# Project_Arduino_DUE_shield.net
KiCad netlist of a schematic drawn in Altium Designer
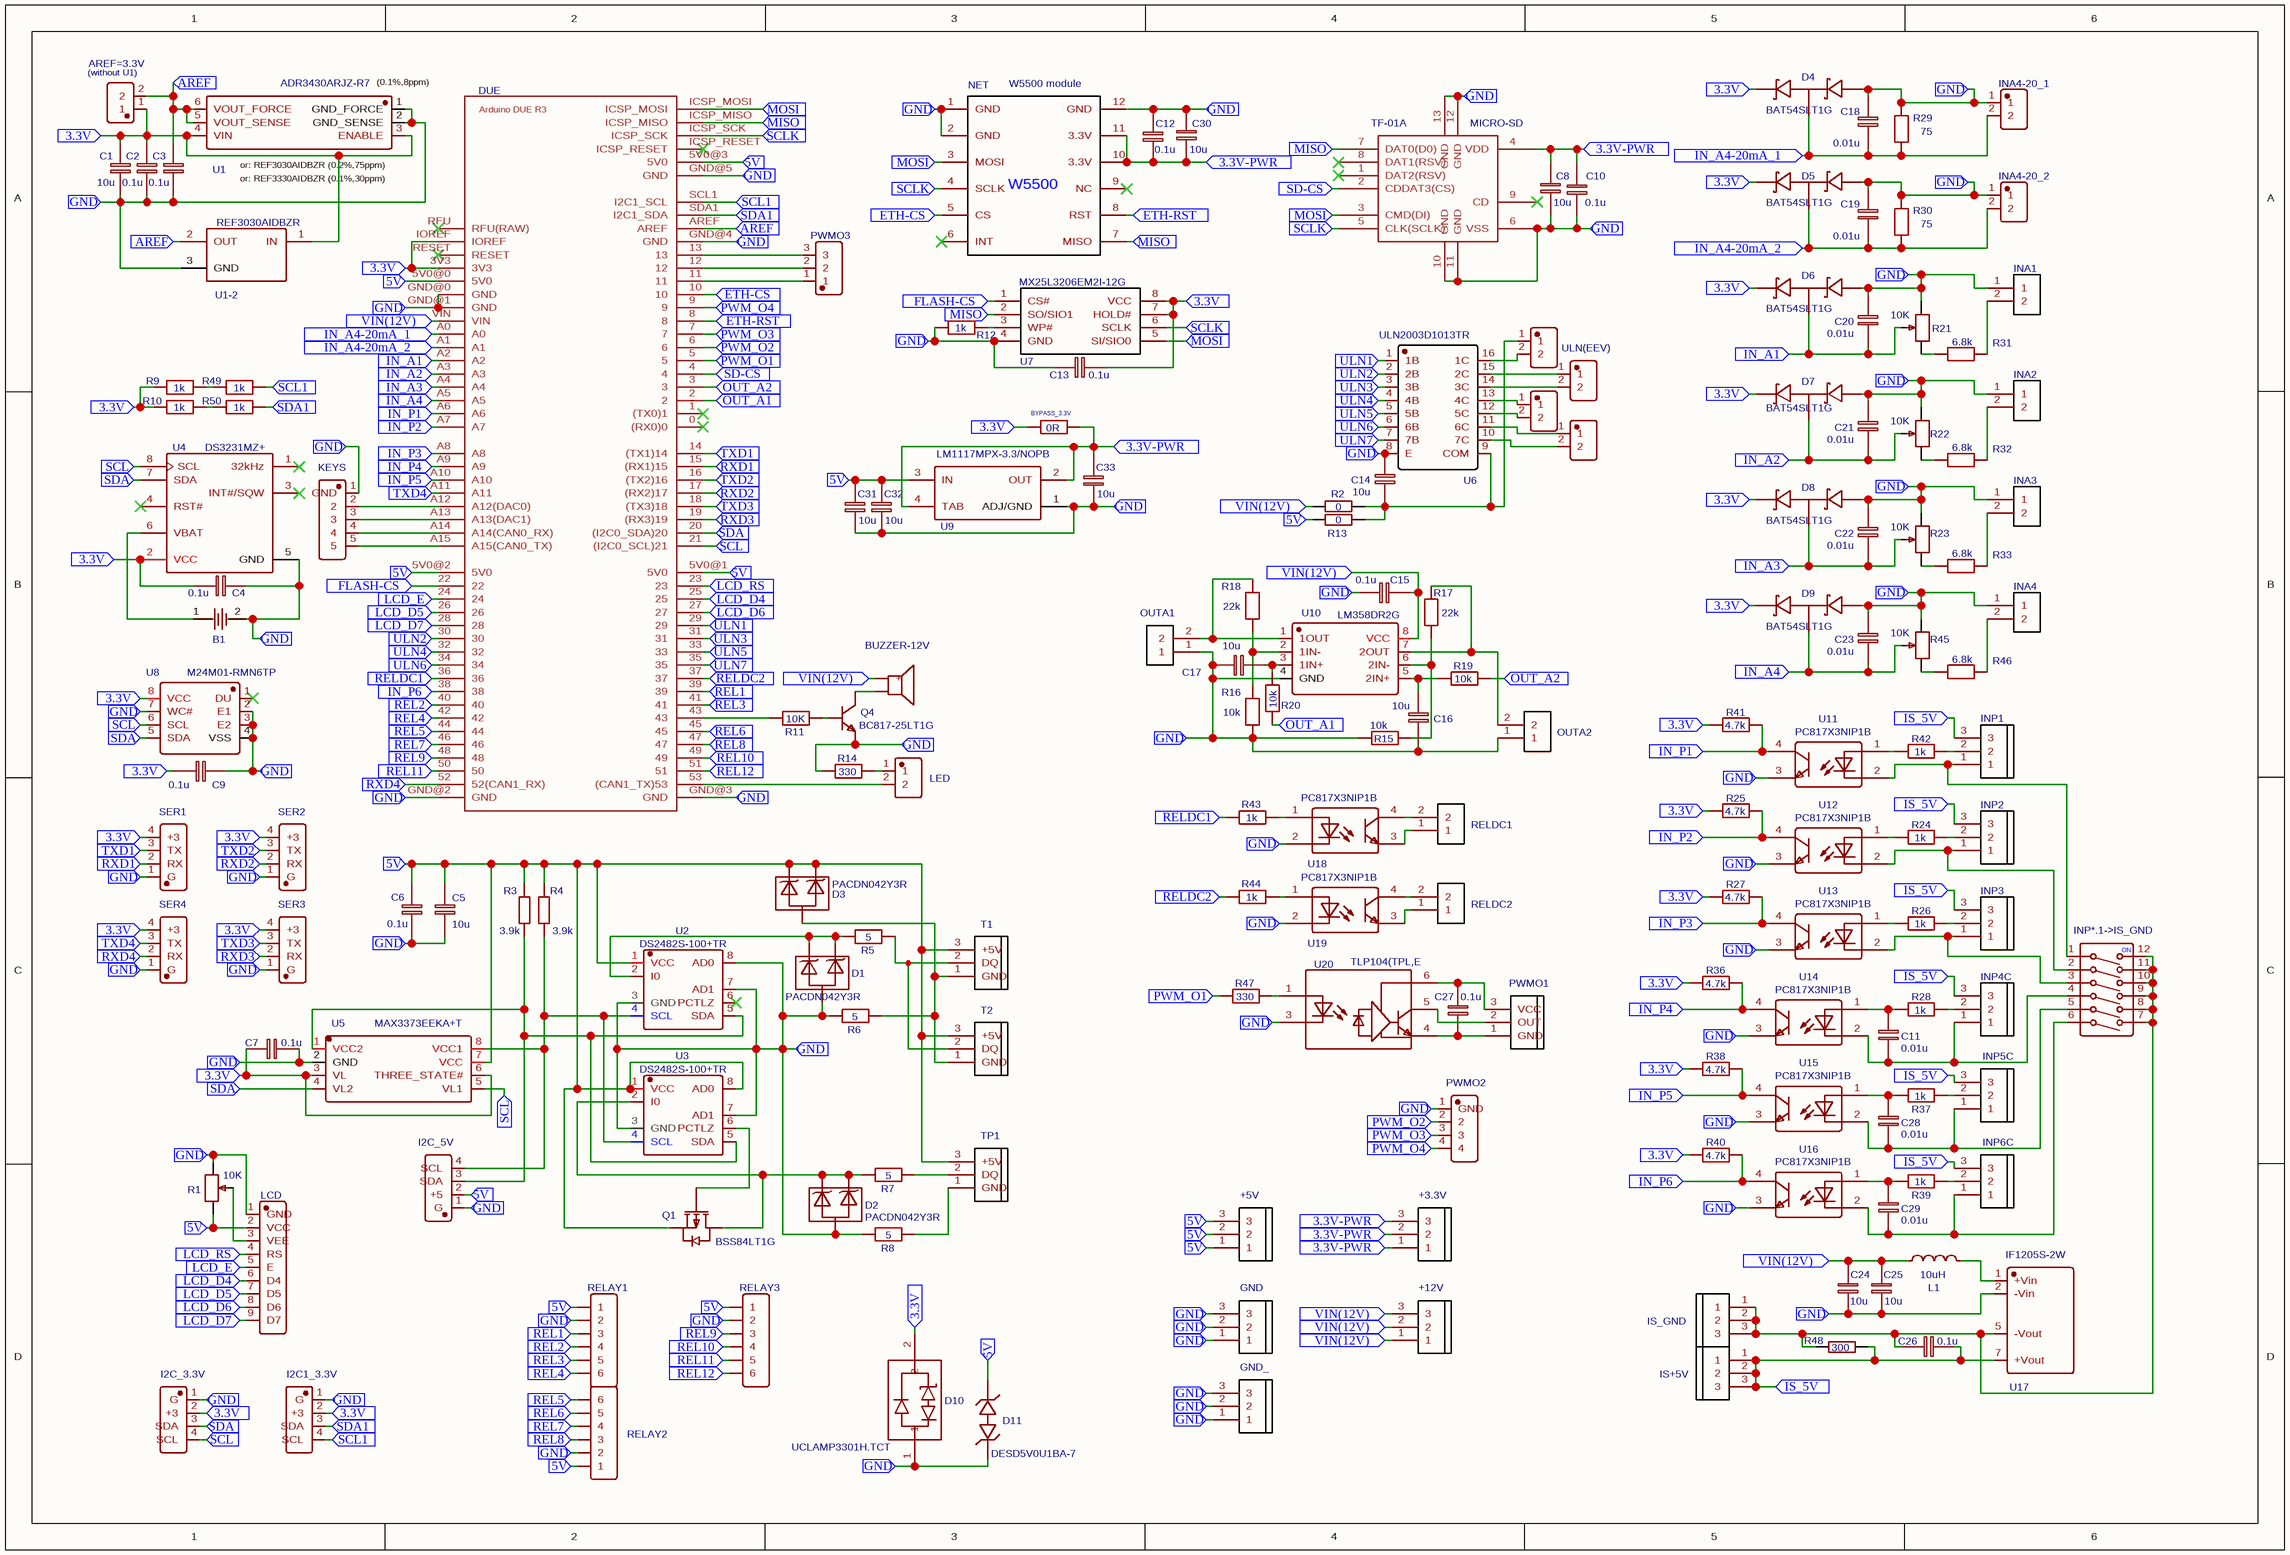
[diagram p0: Project_Arduino DUE shield.schdoc]

(export (version "E")
  (design (tool "Eeschema 10.0.6"))
  (components
    (comp (ref "+3.3V")
      (value "KF128L-5.08-3P")
      (fields (field (name "BOM_SUPPLIER PART") "C474941"))
      (libsource (lib "altium-import") (part "root_3_KF128L-5.08-3P_"))
    )
    (comp (ref "+5V")
      (value "KF128L-5.08-3P")
      (fields (field (name "BOM_SUPPLIER PART") "C474941"))
      (libsource (lib "altium-import") (part "root_3_KF128L-5.08-3P_"))
    )
    (comp (ref "+12V")
      (value "KF128L-5.08-3P")
      (fields (field (name "BOM_SUPPLIER PART") "C474941"))
      (libsource (lib "altium-import") (part "root_3_KF128L-5.08-3P_"))
    )
    (comp (ref "AREF=3.3V")
      (value "A2541WV-2P")
      (fields (field (name "BOM_SUPPLIER PART") "C225477") (field (name "CONTRIBUTOR") "LCSC"))
      (libsource (lib "altium-import") (part "root_2_A2541WV-2P_"))
    )
    (comp (ref "B1")
      (value "CR2032-BS-2-1")
      (fields (field (name "BOM_MANUFACTURER PART") "BS-2-1") (field (name "BOM_SUPPLIER PART") "C70376"))
      (libsource (lib "altium-import") (part "root_0_CR2032-BS-2-1_"))
    )
    (comp (ref "BUZZER-12V")
      (value "TMB12A12")
      (fields (field (name "BOM_SUPPLIER PART") "C96079"))
      (libsource (lib "altium-import") (part "root_0_TMB12A12_"))
    )
    (comp (ref "BYPASS_3.3V")
      (value "0R")
      (fields (field (name "CONTRIBUTOR") "LCEDA_Lib"))
      (libsource (lib "altium-import") (part "root_0_0R_"))
    )
    (comp (ref "C1")
      (value "10u")
      (fields
        (field (name "BOM_MANUFACTURER PART") "CL21A106KAYNNNE")
        (field (name "BOM_SUPPLIER PART") "C15850")
      )
      (libsource (lib "altium-import") (part "root_0_10u_"))
    )
    (comp (ref "C2")
      (value "0.1u")
      (fields
        (field (name "BOM_MANUFACTURER PART") "CC0603KRX7R9BB104")
        (field (name "BOM_SUPPLIER PART") "C14663")
      )
      (libsource (lib "") (part "root_0_0.1u__1"))
    )
    (comp (ref "C3")
      (value "0.1u")
      (fields
        (field (name "BOM_MANUFACTURER PART") "CC0603KRX7R9BB104")
        (field (name "BOM_SUPPLIER PART") "C14663")
      )
      (libsource (lib "") (part "root_0_0.1u__1"))
    )
    (comp (ref "C4")
      (value "0.1u")
      (fields
        (field (name "BOM_MANUFACTURER PART") "CC0603KRX7R9BB104")
        (field (name "BOM_SUPPLIER PART") "C14663")
      )
      (libsource (lib "altium-import") (part "root_3_0.1u_"))
    )
    (comp (ref "C5")
      (value "10u")
      (fields
        (field (name "BOM_MANUFACTURER PART") "CL21A106KAYNNNE")
        (field (name "BOM_SUPPLIER PART") "C15850")
      )
      (libsource (lib "altium-import") (part "root_0_10u_"))
    )
    (comp (ref "C6")
      (value "0.1u")
      (fields
        (field (name "BOM_MANUFACTURER PART") "CC0603KRX7R9BB104")
        (field (name "BOM_SUPPLIER PART") "C14663")
      )
      (libsource (lib "") (part "root_0_0.1u__1"))
    )
    (comp (ref "C7")
      (value "0.1u")
      (fields
        (field (name "BOM_MANUFACTURER PART") "CC0603KRX7R9BB104")
        (field (name "BOM_SUPPLIER PART") "C14663")
      )
      (libsource (lib "") (part "root_1_0.1u__1"))
    )
    (comp (ref "C8")
      (value "10u")
      (fields
        (field (name "BOM_SUPPLIER PART") "C15850")
        (field (name "BOM_MANUFACTURER PART") "CL21A106KAYNNNE")
        (field (name "CONTRIBUTOR") "LCEDA_Lib")
      )
      (libsource (lib "altium-import") (part "root_3_10u_"))
    )
    (comp (ref "C9")
      (value "0.1u")
      (fields
        (field (name "BOM_MANUFACTURER PART") "CC0603KRX7R9BB104")
        (field (name "BOM_SUPPLIER PART") "C14663")
      )
      (libsource (lib "altium-import") (part "root_3_0.1u_"))
    )
    (comp (ref "C10")
      (value "0.1u")
      (fields
        (field (name "BOM_SUPPLIER PART") "C14663")
        (field (name "BOM_MANUFACTURER PART") "CC0603KRX7R9BB104")
        (field (name "CONTRIBUTOR") "LCEDA_Lib")
      )
      (libsource (lib "altium-import") (part "root_1_0.1u_"))
    )
    (comp (ref "C11")
      (value "0.01u")
      (fields
        (field (name "BOM_SUPPLIER PART") "C57112")
        (field (name "BOM_MANUFACTURER PART") "0603B103K500NT")
        (field (name "CONTRIBUTOR") "LCEDA_Lib")
      )
      (libsource (lib "altium-import") (part "root_3_0.01u_"))
    )
    (comp (ref "C12")
      (value "0.1u")
      (fields
        (field (name "BOM_SUPPLIER PART") "C14663")
        (field (name "BOM_MANUFACTURER PART") "CC0603KRX7R9BB104")
        (field (name "CONTRIBUTOR") "LCEDA_Lib")
      )
      (libsource (lib "altium-import") (part "root_1_0.1u_"))
    )
    (comp (ref "C13")
      (value "0.1u")
      (fields
        (field (name "BOM_SUPPLIER PART") "C14663")
        (field (name "BOM_MANUFACTURER PART") "CC0603KRX7R9BB104")
        (field (name "CONTRIBUTOR") "LCEDA_Lib")
      )
      (libsource (lib "altium-import") (part "root_0_0.1u_"))
    )
    (comp (ref "C14")
      (value "10u")
      (fields
        (field (name "BOM_MANUFACTURER PART") "CL21A106KAYNNNE")
        (field (name "BOM_SUPPLIER PART") "C15850")
      )
      (libsource (lib "") (part "root_0_10u__1"))
    )
    (comp (ref "C15")
      (value "0.1u")
      (fields
        (field (name "BOM_MANUFACTURER PART") "CC0603KRX7R9BB104")
        (field (name "BOM_SUPPLIER PART") "C14663")
      )
      (libsource (lib "") (part "root_3_0.1u__1"))
    )
    (comp (ref "C16")
      (value "10u")
      (fields
        (field (name "BOM_MANUFACTURER PART") "CL21A106KAYNNNE")
        (field (name "BOM_SUPPLIER PART") "C15850")
      )
      (libsource (lib "altium-import") (part "root_0_10u_"))
    )
    (comp (ref "C17")
      (value "10u")
      (fields
        (field (name "BOM_MANUFACTURER PART") "CL21A106KAYNNNE")
        (field (name "BOM_SUPPLIER PART") "C15850")
      )
      (libsource (lib "") (part "root_1_10u__1"))
    )
    (comp (ref "C18")
      (value "0.01u")
      (fields
        (field (name "BOM_MANUFACTURER PART") "0603B103K500NT")
        (field (name "BOM_SUPPLIER PART") "C57112")
      )
      (libsource (lib "altium-import") (part "root_0_0.01u_"))
    )
    (comp (ref "C19")
      (value "0.01u")
      (fields
        (field (name "BOM_MANUFACTURER PART") "0603B103K500NT")
        (field (name "BOM_SUPPLIER PART") "C57112")
      )
      (libsource (lib "altium-import") (part "root_0_0.01u_"))
    )
    (comp (ref "C20")
      (value "0.01u")
      (fields
        (field (name "BOM_MANUFACTURER PART") "0603B103K500NT")
        (field (name "BOM_SUPPLIER PART") "C57112")
      )
      (libsource (lib "altium-import") (part "root_0_0.01u_"))
    )
    (comp (ref "C21")
      (value "0.01u")
      (fields
        (field (name "BOM_MANUFACTURER PART") "0603B103K500NT")
        (field (name "BOM_SUPPLIER PART") "C57112")
      )
      (libsource (lib "altium-import") (part "root_0_0.01u_"))
    )
    (comp (ref "C22")
      (value "0.01u")
      (fields
        (field (name "BOM_MANUFACTURER PART") "0603B103K500NT")
        (field (name "BOM_SUPPLIER PART") "C57112")
      )
      (libsource (lib "altium-import") (part "root_0_0.01u_"))
    )
    (comp (ref "C23")
      (value "0.01u")
      (fields
        (field (name "BOM_MANUFACTURER PART") "0603B103K500NT")
        (field (name "BOM_SUPPLIER PART") "C57112")
      )
      (libsource (lib "altium-import") (part "root_0_0.01u_"))
    )
    (comp (ref "C24")
      (value "10u")
      (fields
        (field (name "BOM_SUPPLIER PART") "C15850")
        (field (name "BOM_MANUFACTURER PART") "CL21A106KAYNNNE")
        (field (name "CONTRIBUTOR") "LCEDA_Lib")
      )
      (libsource (lib "altium-import") (part "root_1_10u_"))
    )
    (comp (ref "C25")
      (value "10u")
      (fields
        (field (name "BOM_SUPPLIER PART") "C15850")
        (field (name "BOM_MANUFACTURER PART") "CL21A106KAYNNNE")
        (field (name "CONTRIBUTOR") "LCEDA_Lib")
      )
      (libsource (lib "altium-import") (part "root_1_10u_"))
    )
    (comp (ref "C26")
      (value "0.1u")
      (fields
        (field (name "BOM_MANUFACTURER PART") "CC0603KRX7R9BB104")
        (field (name "BOM_SUPPLIER PART") "C14663")
      )
      (libsource (lib "") (part "root_1_0.1u__2"))
    )
    (comp (ref "C27")
      (value "0.1u")
      (fields
        (field (name "BOM_MANUFACTURER PART") "CC0603KRX7R9BB104")
        (field (name "BOM_SUPPLIER PART") "C14663")
      )
      (libsource (lib "") (part "root_0_0.1u__2"))
    )
    (comp (ref "C28")
      (value "0.01u")
      (fields
        (field (name "BOM_SUPPLIER PART") "C57112")
        (field (name "BOM_MANUFACTURER PART") "0603B103K500NT")
        (field (name "CONTRIBUTOR") "LCEDA_Lib")
      )
      (libsource (lib "altium-import") (part "root_3_0.01u_"))
    )
    (comp (ref "C29")
      (value "0.01u")
      (fields
        (field (name "BOM_SUPPLIER PART") "C57112")
        (field (name "BOM_MANUFACTURER PART") "0603B103K500NT")
        (field (name "CONTRIBUTOR") "LCEDA_Lib")
      )
      (libsource (lib "altium-import") (part "root_3_0.01u_"))
    )
    (comp (ref "C30")
      (value "10u")
      (fields
        (field (name "BOM_SUPPLIER PART") "C15850")
        (field (name "BOM_MANUFACTURER PART") "CL21A106KAYNNNE")
        (field (name "CONTRIBUTOR") "LCEDA_Lib")
      )
      (libsource (lib "altium-import") (part "root_3_10u_"))
    )
    (comp (ref "C31")
      (value "10u")
      (fields
        (field (name "BOM_MANUFACTURER PART") "CL21A106KAYNNNE")
        (field (name "BOM_SUPPLIER PART") "C15850")
      )
      (libsource (lib "altium-import") (part "root_2_10u_"))
    )
    (comp (ref "C32")
      (value "10u")
      (fields
        (field (name "BOM_MANUFACTURER PART") "CL21A106KAYNNNE")
        (field (name "BOM_SUPPLIER PART") "C15850")
      )
      (libsource (lib "altium-import") (part "root_2_10u_"))
    )
    (comp (ref "C33")
      (value "10u")
      (fields
        (field (name "BOM_MANUFACTURER PART") "CL21A106KAYNNNE")
        (field (name "BOM_SUPPLIER PART") "C15850")
      )
      (libsource (lib "altium-import") (part "root_2_10u_"))
    )
    (comp (ref "D1")
      (value "PACDN042Y3R")
      (fields (field (name "BOM_SUPPLIER PART") "C233486") (field (name "CONTRIBUTOR") "LCSC"))
      (libsource (lib "altium-import") (part "root_2_PACDN042Y3R_"))
    )
    (comp (ref "D2")
      (value "PACDN042Y3R")
      (fields (field (name "BOM_SUPPLIER PART") "C233486") (field (name "CONTRIBUTOR") "LCSC"))
      (libsource (lib "altium-import") (part "root_2_PACDN042Y3R_"))
    )
    (comp (ref "D3")
      (value "PACDN042Y3R")
      (fields (field (name "BOM_SUPPLIER PART") "C233486") (field (name "CONTRIBUTOR") "LCSC"))
      (libsource (lib "altium-import") (part "root_2_PACDN042Y3R_"))
    )
    (comp (ref "D4")
      (value "BAT54SLT1G")
      (fields (field (name "BOM_SUPPLIER PART") "C19726"))
      (libsource (lib "altium-import") (part "root_0_BAT54SLT1G_"))
    )
    (comp (ref "D5")
      (value "BAT54SLT1G")
      (fields (field (name "BOM_SUPPLIER PART") "C19726"))
      (libsource (lib "altium-import") (part "root_0_BAT54SLT1G_"))
    )
    (comp (ref "D6")
      (value "BAT54SLT1G")
      (fields (field (name "BOM_SUPPLIER PART") "C19726"))
      (libsource (lib "altium-import") (part "root_0_BAT54SLT1G_"))
    )
    (comp (ref "D7")
      (value "BAT54SLT1G")
      (fields (field (name "BOM_SUPPLIER PART") "C19726"))
      (libsource (lib "altium-import") (part "root_0_BAT54SLT1G_"))
    )
    (comp (ref "D8")
      (value "BAT54SLT1G")
      (fields (field (name "BOM_SUPPLIER PART") "C19726"))
      (libsource (lib "altium-import") (part "root_0_BAT54SLT1G_"))
    )
    (comp (ref "D9")
      (value "BAT54SLT1G")
      (fields (field (name "BOM_SUPPLIER PART") "C19726"))
      (libsource (lib "altium-import") (part "root_0_BAT54SLT1G_"))
    )
    (comp (ref "D10")
      (value "UCLAMP3301H.TCT")
      (fields (field (name "BOM_SUPPLIER PART") "C117558") (field (name "CONTRIBUTOR") "LCSC"))
      (libsource (lib "altium-import") (part "root_1_UCLAMP3301H.TCT_"))
    )
    (comp (ref "D11")
      (value "DESD5V0U1BA-7")
      (fields (field (name "BOM_SUPPLIER PART") "C460442") (field (name "CONTRIBUTOR") "LCSC"))
      (libsource (lib "altium-import") (part "root_1_DESD5V0U1BA-7_"))
    )
    (comp (ref "DUE")
      (value "PA_DUE_BRD")
      (description "PatternAgents Due Shield Board Pattern")
      (fields (field (name "BOM_MANUFACTURER PART") "?") (field (name "CONTRIBUTOR") "PatternAgents"))
      (libsource (lib "altium-import") (part "root_0_PA_DUE_BRD_"))
    )
    (comp (ref "GND")
      (value "KF128L-5.08-3P")
      (fields (field (name "BOM_SUPPLIER PART") "C474941"))
      (libsource (lib "altium-import") (part "root_3_KF128L-5.08-3P_"))
    )
    (comp (ref "GND_")
      (value "KF128L-5.08-3P")
      (fields (field (name "BOM_SUPPLIER PART") "C474941"))
      (libsource (lib "altium-import") (part "root_3_KF128L-5.08-3P_"))
    )
    (comp (ref "I2C1_3.3V")
      (value "A2541WV-4P")
      (fields (field (name "BOM_SUPPLIER PART") "C225479") (field (name "CONTRIBUTOR") "LCSC"))
      (libsource (lib "") (part "root_1_A2541WV-4P__2"))
    )
    (comp (ref "I2C_3.3V")
      (value "A2541WV-4P")
      (fields (field (name "BOM_SUPPLIER PART") "C225479") (field (name "CONTRIBUTOR") "LCSC"))
      (libsource (lib "") (part "root_1_A2541WV-4P__2"))
    )
    (comp (ref "I2C_5V")
      (value "A2541WV-4P")
      (fields (field (name "BOM_SUPPLIER PART") "C225479") (field (name "CONTRIBUTOR") "LCSC"))
      (libsource (lib "altium-import") (part "root_1_A2541WV-4P_"))
    )
    (comp (ref "INA1")
      (value "KF128L-5.08-2P")
      (fields (field (name "BOM_SUPPLIER PART") "C474940"))
      (libsource (lib "altium-import") (part "root_3_KF128L-5.08-2P_"))
    )
    (comp (ref "INA2")
      (value "KF128L-5.08-2P")
      (fields (field (name "BOM_SUPPLIER PART") "C474940"))
      (libsource (lib "altium-import") (part "root_3_KF128L-5.08-2P_"))
    )
    (comp (ref "INA3")
      (value "KF128L-5.08-2P")
      (fields (field (name "BOM_SUPPLIER PART") "C474940"))
      (libsource (lib "altium-import") (part "root_3_KF128L-5.08-2P_"))
    )
    (comp (ref "INA4")
      (value "KF128L-5.08-2P")
      (fields (field (name "BOM_SUPPLIER PART") "C474940"))
      (libsource (lib "altium-import") (part "root_3_KF128L-5.08-2P_"))
    )
    (comp (ref "INA4-20_1")
      (value "KF128L-3.5-2P")
      (fields (field (name "BOM_SUPPLIER PART") "C474930") (field (name "CONTRIBUTOR") "LCSC"))
      (libsource (lib "altium-import") (part "root_0_KF128L-3.5-2P_"))
    )
    (comp (ref "INA4-20_2")
      (value "KF128L-3.5-2P")
      (fields (field (name "BOM_SUPPLIER PART") "C474930") (field (name "CONTRIBUTOR") "LCSC"))
      (libsource (lib "altium-import") (part "root_0_KF128L-3.5-2P_"))
    )
    (comp (ref "INP*.1->IS_GND")
      (value "EM-06-Q")
      (fields (field (name "BOM_SUPPLIER PART") "C501580") (field (name "CONTRIBUTOR") "LCSC"))
      (libsource (lib "altium-import") (part "root_3_EM-06-Q_"))
    )
    (comp (ref "INP1")
      (value "KF128L-5.08-3P")
      (fields (field (name "BOM_SUPPLIER PART") "C474941"))
      (libsource (lib "altium-import") (part "root_3_KF128L-5.08-3P_"))
    )
    (comp (ref "INP2")
      (value "KF128L-5.08-3P")
      (fields (field (name "BOM_SUPPLIER PART") "C474941"))
      (libsource (lib "altium-import") (part "root_3_KF128L-5.08-3P_"))
    )
    (comp (ref "INP3")
      (value "KF128L-5.08-3P")
      (fields (field (name "BOM_SUPPLIER PART") "C474941"))
      (libsource (lib "altium-import") (part "root_3_KF128L-5.08-3P_"))
    )
    (comp (ref "INP4C")
      (value "KF128L-5.08-3P")
      (fields (field (name "BOM_SUPPLIER PART") "C474941"))
      (libsource (lib "altium-import") (part "root_3_KF128L-5.08-3P_"))
    )
    (comp (ref "INP5C")
      (value "KF128L-5.08-3P")
      (fields (field (name "BOM_SUPPLIER PART") "C474941"))
      (libsource (lib "altium-import") (part "root_3_KF128L-5.08-3P_"))
    )
    (comp (ref "INP6C")
      (value "KF128L-5.08-3P")
      (fields (field (name "BOM_SUPPLIER PART") "C474941"))
      (libsource (lib "altium-import") (part "root_3_KF128L-5.08-3P_"))
    )
    (comp (ref "IS+5V")
      (value "KF128L-5.08-3P")
      (fields (field (name "BOM_SUPPLIER PART") "C474941"))
      (libsource (lib "altium-import") (part "root_1_KF128L-5.08-3P_"))
    )
    (comp (ref "IS_GND")
      (value "KF128L-5.08-3P")
      (fields (field (name "BOM_SUPPLIER PART") "C474941"))
      (libsource (lib "altium-import") (part "root_1_KF128L-5.08-3P_"))
    )
    (comp (ref "KEYS")
      (value "A2541WV-5P")
      (fields (field (name "BOM_SUPPLIER PART") "C225480") (field (name "CONTRIBUTOR") "LCSC"))
      (libsource (lib "altium-import") (part "root_1_A2541WV-5P_"))
    )
    (comp (ref "L1")
      (value "10uH")
      (fields
        (field (name "BOM_MANUFACTURER PART") "FNR4018S100MT")
        (field (name "BOM_SUPPLIER PART") "C167808")
        (field (name "CONTRIBUTOR") "LCSC")
      )
      (libsource (lib "altium-import") (part "root_0_10uH_"))
    )
    (comp (ref "LCD")
      (value "PZ254V-11-09P")
      (fields (field (name "BOM_SUPPLIER PART") "C492408") (field (name "CONTRIBUTOR") "LCSC"))
      (libsource (lib "altium-import") (part "root_0_PZ254V-11-09P_"))
    )
    (comp (ref "LED")
      (value "A2541WV-2P")
      (fields (field (name "BOM_SUPPLIER PART") "C225477") (field (name "CONTRIBUTOR") "LCSC"))
      (libsource (lib "altium-import") (part "root_0_A2541WV-2P_"))
    )
    (comp (ref "MICRO-SD")
      (value "TF-01A")
      (fields (field (name "BOM_MANUFACTURER PART") "TF-15×15") (field (name "BOM_SUPPLIER PART") "C111196"))
      (libsource (lib "altium-import") (part "root_0_TF-01A_"))
    )
    (comp (ref "NET")
      (value "W5500 module")
      (fields (field (name "BOM_MANUFACTURER PART") "?") (field (name "CONTRIBUTOR") "RubenDijk"))
      (libsource (lib "altium-import") (part "root_0_W5500 module_"))
    )
    (comp (ref "OUTA1")
      (value "KF128L-5.08-2P")
      (fields
        (field (name "BOM_MANUFACTURER PART") "KF128L-3.5-2P")
        (field (name "BOM_SUPPLIER PART") "C474930")
      )
      (libsource (lib "altium-import") (part "root_1_KF128L-5.08-2P_"))
    )
    (comp (ref "OUTA2")
      (value "KF128L-5.08-2P")
      (fields
        (field (name "BOM_MANUFACTURER PART") "KF128L-3.5-2P")
        (field (name "BOM_SUPPLIER PART") "C474930")
      )
      (libsource (lib "") (part "root_3_KF128L-5.08-2P__1"))
    )
    (comp (ref "PWMO1")
      (value "KF128L-5.08-3P")
      (fields (field (name "BOM_SUPPLIER PART") "C474941"))
      (libsource (lib "altium-import") (part "root_3_KF128L-5.08-3P_"))
    )
    (comp (ref "PWMO2")
      (value "A2541WV-4P")
      (fields (field (name "BOM_SUPPLIER PART") "C225479") (field (name "CONTRIBUTOR") "LCSC"))
      (libsource (lib "") (part "root_1_A2541WV-4P__1"))
    )
    (comp (ref "PWMO3")
      (value "A2541WV-3P")
      (fields (field (name "BOM_SUPPLIER PART") "C225478") (field (name "CONTRIBUTOR") "LCSC"))
      (libsource (lib "altium-import") (part "root_3_A2541WV-3P_"))
    )
    (comp (ref "Q1")
      (value "BSS84LT1G")
      (fields (field (name "BOM_MANUFACTURER PART") "LBSS84LT1G") (field (name "BOM_SUPPLIER PART") "C8492"))
      (libsource (lib "altium-import") (part "root_3_BSS84LT1G_"))
    )
    (comp (ref "Q4")
      (value "BC817-25LT1G")
      (fields (field (name "BOM_SUPPLIER PART") "C82635"))
      (libsource (lib "altium-import") (part "root_0_BC817-25LT1G_"))
    )
    (comp (ref "R1")
      (value "10K")
      (fields
        (field (name "BOM_MANUFACTURER PART") "3314J-1-103E")
        (field (name "BOM_SUPPLIER PART") "C36376")
      )
      (libsource (lib "") (part "root_0_10K__1"))
    )
    (comp (ref "R2") (value "0") (libsource (lib "altium-import") (part "root_0_0_")))
    (comp (ref "R3")
      (value "3.9k")
      (fields
        (field (name "BOM_MANUFACTURER PART") "0603WAF3901T5E")
        (field (name "BOM_SUPPLIER PART") "C23018")
      )
      (libsource (lib "altium-import") (part "root_1_3.9k_"))
    )
    (comp (ref "R4")
      (value "3.9k")
      (fields
        (field (name "BOM_MANUFACTURER PART") "0603WAF3901T5E")
        (field (name "BOM_SUPPLIER PART") "C23018")
      )
      (libsource (lib "altium-import") (part "root_1_3.9k_"))
    )
    (comp (ref "R5")
      (value "5")
      (fields
        (field (name "BOM_SUPPLIER PART") "C25197")
        (field (name "BOM_MANUFACTURER PART") "0603WAF510KT5E")
        (field (name "CONTRIBUTOR") "LCEDA_Lib")
      )
      (libsource (lib "altium-import") (part "root_0_5_"))
    )
    (comp (ref "R6")
      (value "5")
      (fields
        (field (name "BOM_SUPPLIER PART") "C25197")
        (field (name "BOM_MANUFACTURER PART") "0603WAF510KT5E")
        (field (name "CONTRIBUTOR") "LCEDA_Lib")
      )
      (libsource (lib "altium-import") (part "root_0_5_"))
    )
    (comp (ref "R7")
      (value "5")
      (fields
        (field (name "BOM_SUPPLIER PART") "C25197")
        (field (name "BOM_MANUFACTURER PART") "0603WAF510KT5E")
        (field (name "CONTRIBUTOR") "LCEDA_Lib")
      )
      (libsource (lib "altium-import") (part "root_0_5_"))
    )
    (comp (ref "R8")
      (value "5")
      (fields
        (field (name "BOM_SUPPLIER PART") "C25197")
        (field (name "BOM_MANUFACTURER PART") "0603WAF510KT5E")
        (field (name "CONTRIBUTOR") "LCEDA_Lib")
      )
      (libsource (lib "altium-import") (part "root_0_5_"))
    )
    (comp (ref "R9")
      (value "1k")
      (fields
        (field (name "BOM_SUPPLIER PART") "C21190")
        (field (name "BOM_MANUFACTURER PART") "0603WAF1001T5E")
        (field (name "CONTRIBUTOR") "LCEDA_Lib")
      )
      (libsource (lib "") (part "root_0_1k__1"))
    )
    (comp (ref "R10")
      (value "1k")
      (fields
        (field (name "BOM_SUPPLIER PART") "C21190")
        (field (name "BOM_MANUFACTURER PART") "0603WAF1001T5E")
        (field (name "CONTRIBUTOR") "LCEDA_Lib")
      )
      (libsource (lib "") (part "root_0_1k__1"))
    )
    (comp (ref "R11")
      (value "10K")
      (fields
        (field (name "BOM_MANUFACTURER PART") "0603WAF1002T5E")
        (field (name "BOM_SUPPLIER PART") "C25804")
      )
      (libsource (lib "altium-import") (part "root_2_10K_"))
    )
    (comp (ref "R12")
      (value "1k")
      (fields
        (field (name "BOM_SUPPLIER PART") "C21190")
        (field (name "BOM_MANUFACTURER PART") "0603WAF1001T5E")
        (field (name "CONTRIBUTOR") "LCEDA_Lib")
      )
      (libsource (lib "") (part "root_0_1k__1"))
    )
    (comp (ref "R13") (value "0") (libsource (lib "altium-import") (part "root_0_0_")))
    (comp (ref "R14")
      (value "330")
      (fields
        (field (name "BOM_SUPPLIER PART") "C23138")
        (field (name "BOM_MANUFACTURER PART") "0603WAF3300T5E")
        (field (name "CONTRIBUTOR") "LCEDA_Lib")
      )
      (libsource (lib "altium-import") (part "root_2_330_"))
    )
    (comp (ref "R15")
      (value "10k")
      (fields
        (field (name "BOM_MANUFACTURER PART") "0603WAF1002T5E")
        (field (name "BOM_SUPPLIER PART") "C25804")
      )
      (libsource (lib "altium-import") (part "root_0_10k_"))
    )
    (comp (ref "R16")
      (value "10k")
      (fields
        (field (name "BOM_MANUFACTURER PART") "0603WAF1002T5E")
        (field (name "BOM_SUPPLIER PART") "C25804")
      )
      (libsource (lib "altium-import") (part "root_1_10k_"))
    )
    (comp (ref "R17")
      (value "22k")
      (fields
        (field (name "BOM_MANUFACTURER PART") "0603WAF2202T5E")
        (field (name "BOM_SUPPLIER PART") "C31850")
      )
      (libsource (lib "altium-import") (part "root_1_22k_"))
    )
    (comp (ref "R18")
      (value "22k")
      (fields
        (field (name "BOM_MANUFACTURER PART") "0603WAF2202T5E")
        (field (name "BOM_SUPPLIER PART") "C31850")
      )
      (libsource (lib "altium-import") (part "root_1_22k_"))
    )
    (comp (ref "R19")
      (value "10k")
      (fields
        (field (name "BOM_MANUFACTURER PART") "0603WAF1002T5E")
        (field (name "BOM_SUPPLIER PART") "C25804")
      )
      (libsource (lib "altium-import") (part "root_0_10k_"))
    )
    (comp (ref "R20")
      (value "10k")
      (fields
        (field (name "BOM_MANUFACTURER PART") "0603WAF1002T5E")
        (field (name "BOM_SUPPLIER PART") "C25804")
      )
      (libsource (lib "altium-import") (part "root_1_10k_"))
    )
    (comp (ref "R21")
      (value "10K")
      (fields
        (field (name "BOM_MANUFACTURER PART") "3314J-1-103E")
        (field (name "BOM_SUPPLIER PART") "C36376")
      )
      (libsource (lib "altium-import") (part "root_0_10K_"))
    )
    (comp (ref "R22")
      (value "10K")
      (fields
        (field (name "BOM_MANUFACTURER PART") "3314J-1-103E")
        (field (name "BOM_SUPPLIER PART") "C36376")
      )
      (libsource (lib "altium-import") (part "root_0_10K_"))
    )
    (comp (ref "R23")
      (value "10K")
      (fields
        (field (name "BOM_MANUFACTURER PART") "3314J-1-103E")
        (field (name "BOM_SUPPLIER PART") "C36376")
      )
      (libsource (lib "altium-import") (part "root_0_10K_"))
    )
    (comp (ref "R24")
      (value "1k")
      (fields
        (field (name "BOM_MANUFACTURER PART") "0603WAF1001T5E")
        (field (name "BOM_SUPPLIER PART") "C21190")
      )
      (libsource (lib "altium-import") (part "root_0_1k_"))
    )
    (comp (ref "R25")
      (value "4.7k")
      (fields
        (field (name "BOM_MANUFACTURER PART") "0603WAF4701T5E")
        (field (name "BOM_SUPPLIER PART") "C23162")
      )
      (libsource (lib "altium-import") (part "root_0_4.7k_"))
    )
    (comp (ref "R26")
      (value "1k")
      (fields
        (field (name "BOM_MANUFACTURER PART") "0603WAF1001T5E")
        (field (name "BOM_SUPPLIER PART") "C21190")
      )
      (libsource (lib "altium-import") (part "root_0_1k_"))
    )
    (comp (ref "R27")
      (value "4.7k")
      (fields
        (field (name "BOM_MANUFACTURER PART") "0603WAF4701T5E")
        (field (name "BOM_SUPPLIER PART") "C23162")
      )
      (libsource (lib "altium-import") (part "root_0_4.7k_"))
    )
    (comp (ref "R28")
      (value "1k")
      (fields
        (field (name "BOM_MANUFACTURER PART") "0603WAF1001T5E")
        (field (name "BOM_SUPPLIER PART") "C21190")
      )
      (libsource (lib "altium-import") (part "root_0_1k_"))
    )
    (comp (ref "R29")
      (value "75")
      (fields
        (field (name "BOM_MANUFACTURER PART") "0805W8F750JT5E")
        (field (name "BOM_SUPPLIER PART") "C20638")
      )
      (libsource (lib "altium-import") (part "root_3_75_"))
    )
    (comp (ref "R30")
      (value "75")
      (fields
        (field (name "BOM_MANUFACTURER PART") "0805W8F750JT5E")
        (field (name "BOM_SUPPLIER PART") "C20638")
      )
      (libsource (lib "altium-import") (part "root_3_75_"))
    )
    (comp (ref "R31")
      (value "6.8k")
      (fields
        (field (name "BOM_MANUFACTURER PART") "0603WAF6801T5E")
        (field (name "BOM_SUPPLIER PART") "C23212")
      )
      (libsource (lib "altium-import") (part "root_0_6.8k_"))
    )
    (comp (ref "R32")
      (value "6.8k")
      (fields
        (field (name "BOM_MANUFACTURER PART") "0603WAF6801T5E")
        (field (name "BOM_SUPPLIER PART") "C23212")
      )
      (libsource (lib "altium-import") (part "root_0_6.8k_"))
    )
    (comp (ref "R33")
      (value "6.8k")
      (fields
        (field (name "BOM_MANUFACTURER PART") "0603WAF6801T5E")
        (field (name "BOM_SUPPLIER PART") "C23212")
      )
      (libsource (lib "altium-import") (part "root_0_6.8k_"))
    )
    (comp (ref "R36")
      (value "4.7k")
      (fields
        (field (name "BOM_MANUFACTURER PART") "0603WAF4701T5E")
        (field (name "BOM_SUPPLIER PART") "C23162")
      )
      (libsource (lib "altium-import") (part "root_0_4.7k_"))
    )
    (comp (ref "R37")
      (value "1k")
      (fields
        (field (name "BOM_MANUFACTURER PART") "0603WAF1001T5E")
        (field (name "BOM_SUPPLIER PART") "C21190")
      )
      (libsource (lib "altium-import") (part "root_0_1k_"))
    )
    (comp (ref "R38")
      (value "4.7k")
      (fields
        (field (name "BOM_MANUFACTURER PART") "0603WAF4701T5E")
        (field (name "BOM_SUPPLIER PART") "C23162")
      )
      (libsource (lib "altium-import") (part "root_0_4.7k_"))
    )
    (comp (ref "R39")
      (value "1k")
      (fields
        (field (name "BOM_MANUFACTURER PART") "0603WAF1001T5E")
        (field (name "BOM_SUPPLIER PART") "C21190")
      )
      (libsource (lib "altium-import") (part "root_0_1k_"))
    )
    (comp (ref "R40")
      (value "4.7k")
      (fields
        (field (name "BOM_MANUFACTURER PART") "0603WAF4701T5E")
        (field (name "BOM_SUPPLIER PART") "C23162")
      )
      (libsource (lib "altium-import") (part "root_0_4.7k_"))
    )
    (comp (ref "R41")
      (value "4.7k")
      (fields
        (field (name "BOM_MANUFACTURER PART") "0603WAF4701T5E")
        (field (name "BOM_SUPPLIER PART") "C23162")
      )
      (libsource (lib "altium-import") (part "root_0_4.7k_"))
    )
    (comp (ref "R42")
      (value "1k")
      (fields
        (field (name "BOM_MANUFACTURER PART") "0603WAF1001T5E")
        (field (name "BOM_SUPPLIER PART") "C21190")
      )
      (libsource (lib "altium-import") (part "root_0_1k_"))
    )
    (comp (ref "R43")
      (value "1k")
      (fields
        (field (name "BOM_SUPPLIER PART") "C21190")
        (field (name "BOM_MANUFACTURER PART") "0603WAF1001T5E")
        (field (name "CONTRIBUTOR") "LCEDA_Lib")
      )
      (libsource (lib "") (part "root_0_1k__1"))
    )
    (comp (ref "R44")
      (value "1k")
      (fields
        (field (name "BOM_SUPPLIER PART") "C21190")
        (field (name "BOM_MANUFACTURER PART") "0603WAF1001T5E")
        (field (name "CONTRIBUTOR") "LCEDA_Lib")
      )
      (libsource (lib "") (part "root_0_1k__1"))
    )
    (comp (ref "R45")
      (value "10K")
      (fields
        (field (name "BOM_MANUFACTURER PART") "3314J-1-103E")
        (field (name "BOM_SUPPLIER PART") "C36376")
      )
      (libsource (lib "altium-import") (part "root_0_10K_"))
    )
    (comp (ref "R46")
      (value "6.8k")
      (fields
        (field (name "BOM_MANUFACTURER PART") "0603WAF6801T5E")
        (field (name "BOM_SUPPLIER PART") "C23212")
      )
      (libsource (lib "altium-import") (part "root_0_6.8k_"))
    )
    (comp (ref "R47")
      (value "330")
      (fields
        (field (name "BOM_SUPPLIER PART") "C23138")
        (field (name "BOM_MANUFACTURER PART") "0603WAF3300T5E")
        (field (name "CONTRIBUTOR") "LCEDA_Lib")
      )
      (libsource (lib "altium-import") (part "root_0_330_"))
    )
    (comp (ref "R48")
      (value "300")
      (fields
        (field (name "BOM_MANUFACTURER PART") "1206W4F3000T5E")
        (field (name "BOM_SUPPLIER PART") "C17887")
      )
      (libsource (lib "altium-import") (part "root_0_300_"))
    )
    (comp (ref "R49")
      (value "1k")
      (fields
        (field (name "BOM_SUPPLIER PART") "C21190")
        (field (name "BOM_MANUFACTURER PART") "0603WAF1001T5E")
        (field (name "CONTRIBUTOR") "LCEDA_Lib")
      )
      (libsource (lib "") (part "root_0_1k__1"))
    )
    (comp (ref "R50")
      (value "1k")
      (fields
        (field (name "BOM_SUPPLIER PART") "C21190")
        (field (name "BOM_MANUFACTURER PART") "0603WAF1001T5E")
        (field (name "CONTRIBUTOR") "LCEDA_Lib")
      )
      (libsource (lib "") (part "root_0_1k__1"))
    )
    (comp (ref "RELAY1")
      (value "Header-Male-2.54_1x6")
      (fields (field (name "BOM_SUPPLIER PART") "C37208"))
      (libsource (lib "altium-import") (part "root_0_Header-Male-2.54_1x6_"))
    )
    (comp (ref "RELAY2")
      (value "Header-Male-2.54_1x6")
      (fields (field (name "BOM_SUPPLIER PART") "C37208"))
      (libsource (lib "") (part "root_0_Header-Male-2.54_1x6__1"))
    )
    (comp (ref "RELAY3")
      (value "Header-Male-2.54_1x6")
      (fields (field (name "BOM_SUPPLIER PART") "C37208"))
      (libsource (lib "altium-import") (part "root_0_Header-Male-2.54_1x6_"))
    )
    (comp (ref "RELDC1")
      (value "KF128L-5.08-2P")
      (fields (field (name "BOM_SUPPLIER PART") "C474940"))
      (libsource (lib "") (part "root_3_KF128L-5.08-2P__1"))
    )
    (comp (ref "RELDC2")
      (value "KF128L-5.08-2P")
      (fields (field (name "BOM_SUPPLIER PART") "C474940"))
      (libsource (lib "") (part "root_3_KF128L-5.08-2P__1"))
    )
    (comp (ref "SER1")
      (value "A2541WV-4P")
      (fields (field (name "BOM_SUPPLIER PART") "C225479") (field (name "CONTRIBUTOR") "LCSC"))
      (libsource (lib "altium-import") (part "root_3_A2541WV-4P_"))
    )
    (comp (ref "SER2")
      (value "A2541WV-4P")
      (fields (field (name "BOM_SUPPLIER PART") "C225479") (field (name "CONTRIBUTOR") "LCSC"))
      (libsource (lib "altium-import") (part "root_3_A2541WV-4P_"))
    )
    (comp (ref "SER3")
      (value "A2541WV-4P")
      (fields (field (name "BOM_SUPPLIER PART") "C225479") (field (name "CONTRIBUTOR") "LCSC"))
      (libsource (lib "altium-import") (part "root_3_A2541WV-4P_"))
    )
    (comp (ref "SER4")
      (value "A2541WV-4P")
      (fields (field (name "BOM_SUPPLIER PART") "C225479") (field (name "CONTRIBUTOR") "LCSC"))
      (libsource (lib "altium-import") (part "root_3_A2541WV-4P_"))
    )
    (comp (ref "T1")
      (value "KF128L-5.08-3P")
      (fields (field (name "BOM_SUPPLIER PART") "C474941"))
      (libsource (lib "altium-import") (part "root_3_KF128L-5.08-3P_"))
    )
    (comp (ref "T2")
      (value "KF128L-5.08-3P")
      (fields (field (name "BOM_SUPPLIER PART") "C474941"))
      (libsource (lib "altium-import") (part "root_3_KF128L-5.08-3P_"))
    )
    (comp (ref "TP1")
      (value "KF128L-5.08-3P")
      (fields (field (name "BOM_SUPPLIER PART") "C474941"))
      (libsource (lib "altium-import") (part "root_3_KF128L-5.08-3P_"))
    )
    (comp (ref "U1")
      (value "ADR3430ARJZ-R7")
      (fields (field (name "BOM_SUPPLIER PART") "C138535") (field (name "CONTRIBUTOR") "LCSC"))
      (libsource (lib "altium-import") (part "root_0_ADR3430ARJZ-R7_"))
    )
    (comp (ref "U1-2")
      (value "REF3030AIDBZR")
      (fields (field (name "BOM_SUPPLIER PART") "C38423"))
      (libsource (lib "altium-import") (part "root_0_REF3030AIDBZR_"))
    )
    (comp (ref "U2")
      (value "DS2482S-100+TR")
      (fields
        (field (name "BOM_MANUFACTURER PART") "DS2482S-100+T&R")
        (field (name "BOM_SUPPLIER PART") "C143306")
        (field (name "CONTRIBUTOR") "LCSC")
      )
      (libsource (lib "altium-import") (part "root_0_DS2482S-100+TR_"))
    )
    (comp (ref "U3")
      (value "DS2482S-100+TR")
      (fields
        (field (name "BOM_MANUFACTURER PART") "DS2482S-100+T&R")
        (field (name "BOM_SUPPLIER PART") "C143306")
        (field (name "CONTRIBUTOR") "LCSC")
      )
      (libsource (lib "altium-import") (part "root_0_DS2482S-100+TR_"))
    )
    (comp (ref "U4")
      (value "DS3231MZ+")
      (fields (field (name "BOM_SUPPLIER PART") "C107410"))
      (libsource (lib "altium-import") (part "root_0_DS3231MZ+_"))
    )
    (comp (ref "U5")
      (value "MAX3373EEKA+T")
      (fields (field (name "BOM_SUPPLIER PART") "C116658") (field (name "CONTRIBUTOR") "LCSC"))
      (libsource (lib "altium-import") (part "root_0_MAX3373EEKA+T_"))
    )
    (comp (ref "U6")
      (value "ULN2003D1013TR")
      (fields (field (name "BOM_MANUFACTURER PART") "ULN2003ADR") (field (name "BOM_SUPPLIER PART") "C7512"))
      (libsource (lib "altium-import") (part "root_0_ULN2003D1013TR_"))
    )
    (comp (ref "U7")
      (value "MX25L3206EM2I-12G")
      (fields (field (name "BOM_SUPPLIER PART") "C16142"))
      (libsource (lib "altium-import") (part "root_0_MX25L3206EM2I-12G_"))
    )
    (comp (ref "U8")
      (value "M24M01-RMN6TP")
      (fields (field (name "BOM_SUPPLIER PART") "C79990"))
      (libsource (lib "altium-import") (part "root_0_M24M01-RMN6TP_"))
    )
    (comp (ref "U9")
      (value "LM1117MPX-3.3/NOPB")
      (fields
        (field (name "BOM_MANUFACTURER PART") "LM1117IMPX-3.3/NOPB")
        (field (name "BOM_SUPPLIER PART") "C23984")
      )
      (libsource (lib "altium-import") (part "root_0_LM1117MPX-3.3/NOPB_"))
    )
    (comp (ref "U10")
      (value "LM358DR2G")
      (fields (field (name "BOM_SUPPLIER PART") "C7950"))
      (libsource (lib "altium-import") (part "root_0_LM358DR2G_"))
    )
    (comp (ref "U11")
      (value "PC817X3NIP1B")
      (fields
        (field (name "BOM_MANUFACTURER PART") "EL357N(C)(TA)-G")
        (field (name "BOM_SUPPLIER PART") "C29981")
        (field (name "CONTRIBUTOR") "LCSC")
      )
      (libsource (lib "altium-import") (part "root_0_PC817X3NIP1B_"))
    )
    (comp (ref "U12")
      (value "PC817X3NIP1B")
      (fields
        (field (name "BOM_MANUFACTURER PART") "EL357N(C)(TA)-G")
        (field (name "BOM_SUPPLIER PART") "C29981")
        (field (name "CONTRIBUTOR") "LCSC")
      )
      (libsource (lib "altium-import") (part "root_0_PC817X3NIP1B_"))
    )
    (comp (ref "U13")
      (value "PC817X3NIP1B")
      (fields
        (field (name "BOM_MANUFACTURER PART") "EL357N(C)(TA)-G")
        (field (name "BOM_SUPPLIER PART") "C29981")
        (field (name "CONTRIBUTOR") "LCSC")
      )
      (libsource (lib "altium-import") (part "root_0_PC817X3NIP1B_"))
    )
    (comp (ref "U14")
      (value "PC817X3NIP1B")
      (fields
        (field (name "BOM_MANUFACTURER PART") "EL357N(C)(TA)-G")
        (field (name "BOM_SUPPLIER PART") "C29981")
        (field (name "CONTRIBUTOR") "LCSC")
      )
      (libsource (lib "altium-import") (part "root_0_PC817X3NIP1B_"))
    )
    (comp (ref "U15")
      (value "PC817X3NIP1B")
      (fields
        (field (name "BOM_MANUFACTURER PART") "EL357N(C)(TA)-G")
        (field (name "BOM_SUPPLIER PART") "C29981")
        (field (name "CONTRIBUTOR") "LCSC")
      )
      (libsource (lib "altium-import") (part "root_0_PC817X3NIP1B_"))
    )
    (comp (ref "U16")
      (value "PC817X3NIP1B")
      (fields
        (field (name "BOM_MANUFACTURER PART") "EL357N(C)(TA)-G")
        (field (name "BOM_SUPPLIER PART") "C29981")
        (field (name "CONTRIBUTOR") "LCSC")
      )
      (libsource (lib "altium-import") (part "root_0_PC817X3NIP1B_"))
    )
    (comp (ref "U17")
      (value "IF1205S-2W")
      (fields (field (name "BOM_SUPPLIER PART") "C494963") (field (name "CONTRIBUTOR") "LCSC"))
      (libsource (lib "altium-import") (part "root_0_IF1205S-2W_"))
    )
    (comp (ref "U18")
      (value "PC817X3NIP1B")
      (fields
        (field (name "BOM_MANUFACTURER PART") "EL357N(C)(TA)-G")
        (field (name "BOM_SUPPLIER PART") "C29981")
        (field (name "CONTRIBUTOR") "LCSC")
      )
      (libsource (lib "") (part "root_0_PC817X3NIP1B__1"))
    )
    (comp (ref "U19")
      (value "PC817X3NIP1B")
      (fields
        (field (name "BOM_MANUFACTURER PART") "EL357N(C)(TA)-G")
        (field (name "BOM_SUPPLIER PART") "C29981")
        (field (name "CONTRIBUTOR") "LCSC")
      )
      (libsource (lib "") (part "root_0_PC817X3NIP1B__1"))
    )
    (comp (ref "U20")
      (value "TLP104(TPL,E")
      (fields (field (name "BOM_SUPPLIER PART") "C48236") (field (name "CONTRIBUTOR") "LCSC"))
      (libsource (lib "altium-import") (part "root_0_TLP104(TPL,E_"))
    )
    (comp (ref "ULN(EEV)")
      (value "KF128L-3.5-2P")
      (fields (field (name "BOM_SUPPLIER PART") "C474930") (field (name "CONTRIBUTOR") "LCSC"))
      (libsource (lib "altium-import") (part "root_0_KF128L-3.5-2P_"))
    )
    (comp (ref "ULN(EEV)1")
      (value "KF128L-3.5-2P")
      (fields (field (name "BOM_SUPPLIER PART") "C474930") (field (name "CONTRIBUTOR") "LCSC"))
      (libsource (lib "altium-import") (part "root_0_KF128L-3.5-2P_"))
    )
    (comp (ref "ULN(EEV)2")
      (value "KF128L-3.5-2P")
      (fields (field (name "BOM_SUPPLIER PART") "C474930") (field (name "CONTRIBUTOR") "LCSC"))
      (libsource (lib "altium-import") (part "root_0_KF128L-3.5-2P_"))
    )
    (comp (ref "ULN(EEV)3")
      (value "KF128L-3.5-2P")
      (fields (field (name "BOM_SUPPLIER PART") "C474930") (field (name "CONTRIBUTOR") "LCSC"))
      (libsource (lib "altium-import") (part "root_0_KF128L-3.5-2P_"))
    )
  )
  (nets
    (net (code "1") (name "/3.3V") (class "Default")
      (node (ref "AREF=3.3V") (pin "1") (pinfunction "1_1") (pintype "passive"))
      (node (ref "BYPASS_3.3V") (pin "1") (pinfunction "1_1") (pintype "passive"))
      (node (ref "C1") (pin "1") (pinfunction "1_1") (pintype "passive"))
      (node (ref "C13") (pin "2") (pinfunction "2_2") (pintype "passive"))
      (node (ref "C2") (pin "1") (pinfunction "1_1") (pintype "passive"))
      (node (ref "C4") (pin "2") (pinfunction "2_2") (pintype "passive"))
      (node (ref "C7") (pin "1") (pinfunction "1_1") (pintype "passive"))
      (node (ref "C9") (pin "2") (pinfunction "2_2") (pintype "passive"))
      (node (ref "D10") (pin "2") (pinfunction "2_2") (pintype "passive"))
      (node (ref "D4") (pin "2") (pinfunction "C_2") (pintype "passive"))
      (node (ref "D5") (pin "2") (pinfunction "C_2") (pintype "passive"))
      (node (ref "D6") (pin "2") (pinfunction "C_2") (pintype "passive"))
      (node (ref "D7") (pin "2") (pinfunction "C_2") (pintype "passive"))
      (node (ref "D8") (pin "2") (pinfunction "C_2") (pintype "passive"))
      (node (ref "D9") (pin "2") (pinfunction "C_2") (pintype "passive"))
      (node (ref "DUE") (pin "3V3") (pinfunction "3V3_3V3") (pintype "passive"))
      (node (ref "DUE") (pin "IOREF") (pinfunction "IOREF_IOREF") (pintype "passive"))
      (node (ref "I2C1_3.3V") (pin "2") (pinfunction "+3_2") (pintype "passive"))
      (node (ref "I2C_3.3V") (pin "2") (pinfunction "+3_2") (pintype "passive"))
      (node (ref "R10") (pin "1") (pinfunction "1_1") (pintype "passive"))
      (node (ref "R25") (pin "2") (pinfunction "2_2") (pintype "passive"))
      (node (ref "R27") (pin "2") (pinfunction "2_2") (pintype "passive"))
      (node (ref "R36") (pin "2") (pinfunction "2_2") (pintype "passive"))
      (node (ref "R38") (pin "2") (pinfunction "2_2") (pintype "passive"))
      (node (ref "R40") (pin "2") (pinfunction "2_2") (pintype "passive"))
      (node (ref "R41") (pin "2") (pinfunction "2_2") (pintype "passive"))
      (node (ref "R9") (pin "1") (pinfunction "1_1") (pintype "passive"))
      (node (ref "SER1") (pin "4") (pinfunction "+3_4") (pintype "passive"))
      (node (ref "SER2") (pin "4") (pinfunction "+3_4") (pintype "passive"))
      (node (ref "SER3") (pin "4") (pinfunction "+3_4") (pintype "passive"))
      (node (ref "SER4") (pin "4") (pinfunction "+3_4") (pintype "passive"))
      (node (ref "U1") (pin "3") (pinfunction "ENABLE_3") (pintype "passive"))
      (node (ref "U1") (pin "4") (pinfunction "VIN_4") (pintype "passive"))
      (node (ref "U1-2") (pin "1") (pinfunction "IN_1") (pintype "passive"))
      (node (ref "U4") (pin "2") (pinfunction "VCC_2") (pintype "passive"))
      (node (ref "U5") (pin "3") (pinfunction "VL_3") (pintype "passive"))
      (node (ref "U5") (pin "6") (pinfunction "THREE_STATE#_6") (pintype "passive"))
      (node (ref "U7") (pin "7") (pinfunction "HOLD#_7") (pintype "passive"))
      (node (ref "U7") (pin "8") (pinfunction "VCC_8") (pintype "passive"))
      (node (ref "U8") (pin "8") (pinfunction "VCC_8") (pintype "passive"))
    )
    (net (code "2") (name "/3.3V-PWR") (class "Default")
      (node (ref "+3.3V") (pin "1") (pinfunction "GND_1") (pintype "passive"))
      (node (ref "+3.3V") (pin "2") (pinfunction "DQ_2") (pintype "passive"))
      (node (ref "+3.3V") (pin "3") (pinfunction "+5V_3") (pintype "passive"))
      (node (ref "BYPASS_3.3V") (pin "2") (pinfunction "2_2") (pintype "passive"))
      (node (ref "C10") (pin "2") (pinfunction "2_2") (pintype "passive"))
      (node (ref "C12") (pin "1") (pinfunction "1_1") (pintype "passive"))
      (node (ref "C30") (pin "2") (pinfunction "2_2") (pintype "passive"))
      (node (ref "C33") (pin "2") (pinfunction "2_2") (pintype "passive"))
      (node (ref "C8") (pin "1") (pinfunction "1_1") (pintype "passive"))
      (node (ref "MICRO-SD") (pin "4") (pinfunction "VDD_4") (pintype "passive"))
      (node (ref "NET") (pin "10") (pinfunction "3.3V_10") (pintype "passive"))
      (node (ref "NET") (pin "11") (pinfunction "3.3V_11") (pintype "passive"))
      (node (ref "U9") (pin "2") (pinfunction "OUT_2") (pintype "passive"))
      (node (ref "U9") (pin "4") (pinfunction "TAB_4") (pintype "passive"))
    )
    (net (code "3") (name "/5V") (class "Default")
      (node (ref "+5V") (pin "1") (pinfunction "GND_1") (pintype "passive"))
      (node (ref "+5V") (pin "2") (pinfunction "DQ_2") (pintype "passive"))
      (node (ref "+5V") (pin "3") (pinfunction "+5V_3") (pintype "passive"))
      (node (ref "C31") (pin "2") (pinfunction "2_2") (pintype "passive"))
      (node (ref "C32") (pin "2") (pinfunction "2_2") (pintype "passive"))
      (node (ref "C5") (pin "1") (pinfunction "1_1") (pintype "passive"))
      (node (ref "C6") (pin "1") (pinfunction "1_1") (pintype "passive"))
      (node (ref "D11") (pin "2") (pinfunction "2_2") (pintype "passive"))
      (node (ref "D3") (pin "1") (pinfunction "1_1") (pintype "passive"))
      (node (ref "D3") (pin "2") (pinfunction "2_2") (pintype "passive"))
      (node (ref "DUE") (pin "5V0@0") (pinfunction "5V0_5V0@0") (pintype "passive"))
      (node (ref "DUE") (pin "5V0@1") (pinfunction "5V0_5V0@1") (pintype "passive"))
      (node (ref "DUE") (pin "5V0@2") (pinfunction "5V0_5V0@2") (pintype "passive"))
      (node (ref "DUE") (pin "5V0@3") (pinfunction "5V0_5V0@3") (pintype "passive"))
      (node (ref "I2C_5V") (pin "2") (pinfunction "+5_2") (pintype "passive"))
      (node (ref "LCD") (pin "2") (pinfunction "VCC_2") (pintype "passive"))
      (node (ref "Q1") (pin "2") (pinfunction "S_2") (pintype "passive"))
      (node (ref "R1") (pin "1") (pinfunction "1_1") (pintype "passive"))
      (node (ref "R13") (pin "1") (pinfunction "1_1") (pintype "passive"))
      (node (ref "R3") (pin "2") (pinfunction "2_2") (pintype "passive"))
      (node (ref "R4") (pin "2") (pinfunction "2_2") (pintype "passive"))
      (node (ref "RELAY1") (pin "1") (pinfunction "1_1") (pintype "passive"))
      (node (ref "RELAY2") (pin "1") (pinfunction "1_1") (pintype "passive"))
      (node (ref "RELAY3") (pin "1") (pinfunction "1_1") (pintype "passive"))
      (node (ref "T1") (pin "3") (pinfunction "+5V_3") (pintype "passive"))
      (node (ref "T2") (pin "3") (pinfunction "+5V_3") (pintype "passive"))
      (node (ref "TP1") (pin "3") (pinfunction "+5V_3") (pintype "passive"))
      (node (ref "U2") (pin "1") (pinfunction "VCC_1") (pintype "passive"))
      (node (ref "U3") (pin "1") (pinfunction "VCC_1") (pintype "passive"))
      (node (ref "U3") (pin "8") (pinfunction "AD0_8") (pintype "passive"))
      (node (ref "U5") (pin "7") (pinfunction "VCC_7") (pintype "passive"))
      (node (ref "U9") (pin "3") (pinfunction "IN_3") (pintype "passive"))
    )
    (net (code "4") (name "/AREF") (class "Default")
      (node (ref "AREF=3.3V") (pin "2") (pinfunction "2_2") (pintype "passive"))
      (node (ref "C3") (pin "1") (pinfunction "1_1") (pintype "passive"))
      (node (ref "DUE") (pin "AREF") (pinfunction "AREF_AREF") (pintype "passive"))
      (node (ref "U1") (pin "5") (pinfunction "VOUT_SENSE_5") (pintype "passive"))
      (node (ref "U1") (pin "6") (pinfunction "VOUT_FORCE_6") (pintype "passive"))
      (node (ref "U1-2") (pin "2") (pinfunction "OUT_2") (pintype "passive"))
    )
    (net (code "5") (name "/ETH-CS") (class "Default")
      (node (ref "DUE") (pin "10") (pinfunction "10_10") (pintype "passive"))
      (node (ref "NET") (pin "5") (pinfunction "CS_5") (pintype "passive"))
    )
    (net (code "6") (name "/ETH-RST") (class "Default")
      (node (ref "DUE") (pin "8") (pinfunction "8_8") (pintype "passive"))
      (node (ref "NET") (pin "8") (pinfunction "RST_8") (pintype "passive"))
    )
    (net (code "7") (name "/FLASH-CS") (class "Default")
      (node (ref "DUE") (pin "22") (pinfunction "22_22") (pintype "passive"))
      (node (ref "U7") (pin "1") (pinfunction "CS#_1") (pintype "passive"))
    )
    (net (code "8") (name "/GND") (class "Default")
      (node (ref "B1") (pin "2") (pinfunction "2_2") (pintype "passive"))
      (node (ref "C1") (pin "2") (pinfunction "2_2") (pintype "passive"))
      (node (ref "C10") (pin "1") (pinfunction "1_1") (pintype "passive"))
      (node (ref "C12") (pin "2") (pinfunction "2_2") (pintype "passive"))
      (node (ref "C13") (pin "1") (pinfunction "1_1") (pintype "passive"))
      (node (ref "C14") (pin "1") (pinfunction "1_1") (pintype "passive"))
      (node (ref "C15") (pin "1") (pinfunction "1_1") (pintype "passive"))
      (node (ref "C16") (pin "2") (pinfunction "2_2") (pintype "passive"))
      (node (ref "C17") (pin "1") (pinfunction "1_1") (pintype "passive"))
      (node (ref "C18") (pin "1") (pinfunction "1_1") (pintype "passive"))
      (node (ref "C19") (pin "1") (pinfunction "1_1") (pintype "passive"))
      (node (ref "C2") (pin "2") (pinfunction "2_2") (pintype "passive"))
      (node (ref "C20") (pin "1") (pinfunction "1_1") (pintype "passive"))
      (node (ref "C21") (pin "1") (pinfunction "1_1") (pintype "passive"))
      (node (ref "C22") (pin "1") (pinfunction "1_1") (pintype "passive"))
      (node (ref "C23") (pin "1") (pinfunction "1_1") (pintype "passive"))
      (node (ref "C24") (pin "1") (pinfunction "1_1") (pintype "passive"))
      (node (ref "C25") (pin "1") (pinfunction "1_1") (pintype "passive"))
      (node (ref "C3") (pin "2") (pinfunction "2_2") (pintype "passive"))
      (node (ref "C30") (pin "1") (pinfunction "1_1") (pintype "passive"))
      (node (ref "C31") (pin "1") (pinfunction "1_1") (pintype "passive"))
      (node (ref "C32") (pin "1") (pinfunction "1_1") (pintype "passive"))
      (node (ref "C33") (pin "1") (pinfunction "1_1") (pintype "passive"))
      (node (ref "C4") (pin "1") (pinfunction "1_1") (pintype "passive"))
      (node (ref "C5") (pin "2") (pinfunction "2_2") (pintype "passive"))
      (node (ref "C6") (pin "2") (pinfunction "2_2") (pintype "passive"))
      (node (ref "C7") (pin "2") (pinfunction "2_2") (pintype "passive"))
      (node (ref "C8") (pin "2") (pinfunction "2_2") (pintype "passive"))
      (node (ref "C9") (pin "1") (pinfunction "1_1") (pintype "passive"))
      (node (ref "D1") (pin "3") (pinfunction "3_3") (pintype "passive"))
      (node (ref "D10") (pin "1") (pinfunction "1_1") (pintype "passive"))
      (node (ref "D11") (pin "1") (pinfunction "1_1") (pintype "passive"))
      (node (ref "D2") (pin "3") (pinfunction "3_3") (pintype "passive"))
      (node (ref "D4") (pin "1") (pinfunction "A_1") (pintype "passive"))
      (node (ref "D5") (pin "1") (pinfunction "A_1") (pintype "passive"))
      (node (ref "D6") (pin "1") (pinfunction "A_1") (pintype "passive"))
      (node (ref "D7") (pin "1") (pinfunction "A_1") (pintype "passive"))
      (node (ref "D8") (pin "1") (pinfunction "A_1") (pintype "passive"))
      (node (ref "D9") (pin "1") (pinfunction "A_1") (pintype "passive"))
      (node (ref "DUE") (pin "GND@0") (pinfunction "GND_GND@0") (pintype "passive"))
      (node (ref "DUE") (pin "GND@1") (pinfunction "GND_GND@1") (pintype "passive"))
      (node (ref "DUE") (pin "GND@2") (pinfunction "GND_GND@2") (pintype "passive"))
      (node (ref "DUE") (pin "GND@3") (pinfunction "GND_GND@3") (pintype "passive"))
      (node (ref "DUE") (pin "GND@4") (pinfunction "GND_GND@4") (pintype "passive"))
      (node (ref "DUE") (pin "GND@5") (pinfunction "GND_GND@5") (pintype "passive"))
      (node (ref "GND") (pin "1") (pinfunction "GND_1") (pintype "passive"))
      (node (ref "GND") (pin "2") (pinfunction "DQ_2") (pintype "passive"))
      (node (ref "GND") (pin "3") (pinfunction "+5V_3") (pintype "passive"))
      (node (ref "GND_") (pin "1") (pinfunction "GND_1") (pintype "passive"))
      (node (ref "GND_") (pin "2") (pinfunction "DQ_2") (pintype "passive"))
      (node (ref "GND_") (pin "3") (pinfunction "+5V_3") (pintype "passive"))
      (node (ref "I2C1_3.3V") (pin "1") (pinfunction "G_1") (pintype "passive"))
      (node (ref "I2C_3.3V") (pin "1") (pinfunction "G_1") (pintype "passive"))
      (node (ref "I2C_5V") (pin "1") (pinfunction "G_1") (pintype "passive"))
      (node (ref "INA1") (pin "1") (pinfunction "1_1") (pintype "passive"))
      (node (ref "INA2") (pin "1") (pinfunction "1_1") (pintype "passive"))
      (node (ref "INA3") (pin "1") (pinfunction "1_1") (pintype "passive"))
      (node (ref "INA4") (pin "1") (pinfunction "1_1") (pintype "passive"))
      (node (ref "INA4-20_1") (pin "1") (pinfunction "1_1") (pintype "passive"))
      (node (ref "INA4-20_2") (pin "1") (pinfunction "1_1") (pintype "passive"))
      (node (ref "KEYS") (pin "1") (pinfunction "GND_1") (pintype "passive"))
      (node (ref "LCD") (pin "1") (pinfunction "GND_1") (pintype "passive"))
      (node (ref "MICRO-SD") (pin "10") (pinfunction "GND_10") (pintype "passive"))
      (node (ref "MICRO-SD") (pin "11") (pinfunction "GND_11") (pintype "passive"))
      (node (ref "MICRO-SD") (pin "12") (pinfunction "GND_12") (pintype "passive"))
      (node (ref "MICRO-SD") (pin "13") (pinfunction "GND_13") (pintype "passive"))
      (node (ref "MICRO-SD") (pin "6") (pinfunction "VSS_6") (pintype "passive"))
      (node (ref "NET") (pin "1") (pinfunction "GND_1") (pintype "passive"))
      (node (ref "NET") (pin "12") (pinfunction "GND_12") (pintype "passive"))
      (node (ref "NET") (pin "2") (pinfunction "GND_2") (pintype "passive"))
      (node (ref "OUTA1") (pin "1") (pinfunction "1_1") (pintype "passive"))
      (node (ref "OUTA2") (pin "1") (pinfunction "1_1") (pintype "passive"))
      (node (ref "PWMO2") (pin "1") (pinfunction "GND_1") (pintype "passive"))
      (node (ref "Q4") (pin "2") (pinfunction "E_2") (pintype "passive"))
      (node (ref "R1") (pin "3") (pinfunction "3_3") (pintype "passive"))
      (node (ref "R12") (pin "1") (pinfunction "1_1") (pintype "passive"))
      (node (ref "R14") (pin "2") (pinfunction "2_2") (pintype "passive"))
      (node (ref "R15") (pin "1") (pinfunction "1_1") (pintype "passive"))
      (node (ref "R16") (pin "1") (pinfunction "1_1") (pintype "passive"))
      (node (ref "R21") (pin "1") (pinfunction "1_1") (pintype "passive"))
      (node (ref "R22") (pin "1") (pinfunction "1_1") (pintype "passive"))
      (node (ref "R23") (pin "1") (pinfunction "1_1") (pintype "passive"))
      (node (ref "R29") (pin "1") (pinfunction "1_1") (pintype "passive"))
      (node (ref "R30") (pin "1") (pinfunction "1_1") (pintype "passive"))
      (node (ref "R45") (pin "1") (pinfunction "1_1") (pintype "passive"))
      (node (ref "R6") (pin "1") (pinfunction "1_1") (pintype "passive"))
      (node (ref "R8") (pin "1") (pinfunction "1_1") (pintype "passive"))
      (node (ref "RELAY1") (pin "2") (pinfunction "2_2") (pintype "passive"))
      (node (ref "RELAY2") (pin "2") (pinfunction "2_2") (pintype "passive"))
      (node (ref "RELAY3") (pin "2") (pinfunction "2_2") (pintype "passive"))
      (node (ref "SER1") (pin "1") (pinfunction "G_1") (pintype "passive"))
      (node (ref "SER2") (pin "1") (pinfunction "G_1") (pintype "passive"))
      (node (ref "SER3") (pin "1") (pinfunction "G_1") (pintype "passive"))
      (node (ref "SER4") (pin "1") (pinfunction "G_1") (pintype "passive"))
      (node (ref "U1") (pin "1") (pinfunction "GND_FORCE_1") (pintype "passive"))
      (node (ref "U1") (pin "2") (pinfunction "GND_SENSE_2") (pintype "passive"))
      (node (ref "U1-2") (pin "3") (pinfunction "GND_3") (pintype "passive"))
      (node (ref "U10") (pin "4") (pinfunction "GND_4") (pintype "passive"))
      (node (ref "U11") (pin "3") (pinfunction "EM_3") (pintype "passive"))
      (node (ref "U12") (pin "3") (pinfunction "EM_3") (pintype "passive"))
      (node (ref "U13") (pin "3") (pinfunction "EM_3") (pintype "passive"))
      (node (ref "U14") (pin "3") (pinfunction "EM_3") (pintype "passive"))
      (node (ref "U15") (pin "3") (pinfunction "EM_3") (pintype "passive"))
      (node (ref "U16") (pin "3") (pinfunction "EM_3") (pintype "passive"))
      (node (ref "U17") (pin "2") (pinfunction "-Vin_2") (pintype "passive"))
      (node (ref "U18") (pin "2") (pinfunction "CA_2") (pintype "passive"))
      (node (ref "U19") (pin "2") (pinfunction "CA_2") (pintype "passive"))
      (node (ref "U2") (pin "3") (pinfunction "GND_3") (pintype "passive"))
      (node (ref "U2") (pin "7") (pinfunction "AD1_7") (pintype "passive"))
      (node (ref "U2") (pin "8") (pinfunction "AD0_8") (pintype "passive"))
      (node (ref "U20") (pin "3") (pinfunction "3_3") (pintype "passive"))
      (node (ref "U3") (pin "3") (pinfunction "GND_3") (pintype "passive"))
      (node (ref "U3") (pin "7") (pinfunction "AD1_7") (pintype "passive"))
      (node (ref "U4") (pin "5") (pinfunction "GND_5") (pintype "passive"))
      (node (ref "U5") (pin "2") (pinfunction "GND_2") (pintype "passive"))
      (node (ref "U6") (pin "8") (pinfunction "E_8") (pintype "passive"))
      (node (ref "U7") (pin "4") (pinfunction "GND_4") (pintype "passive"))
      (node (ref "U8") (pin "2") (pinfunction "E1_2") (pintype "passive"))
      (node (ref "U8") (pin "3") (pinfunction "E2_3") (pintype "passive"))
      (node (ref "U8") (pin "4") (pinfunction "VSS_4") (pintype "passive"))
      (node (ref "U8") (pin "7") (pinfunction "WC#_7") (pintype "passive"))
      (node (ref "U9") (pin "1") (pinfunction "ADJ/GND_1") (pintype "passive"))
    )
    (net (code "9") (name "/IN_A1") (class "Default")
      (node (ref "C20") (pin "2") (pinfunction "2_2") (pintype "passive"))
      (node (ref "D6") (pin "3") (pinfunction "A/C_3") (pintype "passive"))
      (node (ref "DUE") (pin "A2") (pinfunction "A2_A2") (pintype "passive"))
      (node (ref "R21") (pin "2") (pinfunction "2_2") (pintype "passive"))
    )
    (net (code "10") (name "/IN_A2") (class "Default")
      (node (ref "C21") (pin "2") (pinfunction "2_2") (pintype "passive"))
      (node (ref "D7") (pin "3") (pinfunction "A/C_3") (pintype "passive"))
      (node (ref "DUE") (pin "A3") (pinfunction "A3_A3") (pintype "passive"))
      (node (ref "R22") (pin "2") (pinfunction "2_2") (pintype "passive"))
    )
    (net (code "11") (name "/IN_A3") (class "Default")
      (node (ref "C22") (pin "2") (pinfunction "2_2") (pintype "passive"))
      (node (ref "D8") (pin "3") (pinfunction "A/C_3") (pintype "passive"))
      (node (ref "DUE") (pin "A4") (pinfunction "A4_A4") (pintype "passive"))
      (node (ref "R23") (pin "2") (pinfunction "2_2") (pintype "passive"))
    )
    (net (code "12") (name "/IN_A4") (class "Default")
      (node (ref "C23") (pin "2") (pinfunction "2_2") (pintype "passive"))
      (node (ref "D9") (pin "3") (pinfunction "A/C_3") (pintype "passive"))
      (node (ref "DUE") (pin "A5") (pinfunction "A5_A5") (pintype "passive"))
      (node (ref "R45") (pin "2") (pinfunction "2_2") (pintype "passive"))
    )
    (net (code "13") (name "/IN_A4-20mA_1") (class "Default")
      (node (ref "C18") (pin "2") (pinfunction "2_2") (pintype "passive"))
      (node (ref "D4") (pin "3") (pinfunction "A/C_3") (pintype "passive"))
      (node (ref "DUE") (pin "A0") (pinfunction "A0_A0") (pintype "passive"))
      (node (ref "INA4-20_1") (pin "2") (pinfunction "2_2") (pintype "passive"))
      (node (ref "R29") (pin "2") (pinfunction "2_2") (pintype "passive"))
    )
    (net (code "14") (name "/IN_A4-20mA_2") (class "Default")
      (node (ref "C19") (pin "2") (pinfunction "2_2") (pintype "passive"))
      (node (ref "D5") (pin "3") (pinfunction "A/C_3") (pintype "passive"))
      (node (ref "DUE") (pin "A1") (pinfunction "A1_A1") (pintype "passive"))
      (node (ref "INA4-20_2") (pin "2") (pinfunction "2_2") (pintype "passive"))
      (node (ref "R30") (pin "2") (pinfunction "2_2") (pintype "passive"))
    )
    (net (code "15") (name "/IN_P1") (class "Default")
      (node (ref "DUE") (pin "A6") (pinfunction "A6_A6") (pintype "passive"))
      (node (ref "R41") (pin "1") (pinfunction "1_1") (pintype "passive"))
      (node (ref "U11") (pin "4") (pinfunction "COL_4") (pintype "passive"))
    )
    (net (code "16") (name "/IN_P2") (class "Default")
      (node (ref "DUE") (pin "A7") (pinfunction "A7_A7") (pintype "passive"))
      (node (ref "R25") (pin "1") (pinfunction "1_1") (pintype "passive"))
      (node (ref "U12") (pin "4") (pinfunction "COL_4") (pintype "passive"))
    )
    (net (code "17") (name "/IN_P3") (class "Default")
      (node (ref "DUE") (pin "A8") (pinfunction "A8_A8") (pintype "passive"))
      (node (ref "R27") (pin "1") (pinfunction "1_1") (pintype "passive"))
      (node (ref "U13") (pin "4") (pinfunction "COL_4") (pintype "passive"))
    )
    (net (code "18") (name "/IN_P4") (class "Default")
      (node (ref "DUE") (pin "A9") (pinfunction "A9_A9") (pintype "passive"))
      (node (ref "R36") (pin "1") (pinfunction "1_1") (pintype "passive"))
      (node (ref "U14") (pin "4") (pinfunction "COL_4") (pintype "passive"))
    )
    (net (code "19") (name "/IN_P5") (class "Default")
      (node (ref "DUE") (pin "A10") (pinfunction "A10_A10") (pintype "passive"))
      (node (ref "R38") (pin "1") (pinfunction "1_1") (pintype "passive"))
      (node (ref "U15") (pin "4") (pinfunction "COL_4") (pintype "passive"))
    )
    (net (code "20") (name "/IN_P6") (class "Default")
      (node (ref "DUE") (pin "38") (pinfunction "38_38") (pintype "passive"))
      (node (ref "R40") (pin "1") (pinfunction "1_1") (pintype "passive"))
      (node (ref "U16") (pin "4") (pinfunction "COL_4") (pintype "passive"))
    )
    (net (code "21") (name "/IS_5V") (class "Default")
      (node (ref "C26") (pin "1") (pinfunction "1_1") (pintype "passive"))
      (node (ref "INP1") (pin "3") (pinfunction "+5V_3") (pintype "passive"))
      (node (ref "INP2") (pin "3") (pinfunction "+5V_3") (pintype "passive"))
      (node (ref "INP3") (pin "3") (pinfunction "+5V_3") (pintype "passive"))
      (node (ref "INP4C") (pin "3") (pinfunction "+5V_3") (pintype "passive"))
      (node (ref "INP5C") (pin "3") (pinfunction "+5V_3") (pintype "passive"))
      (node (ref "INP6C") (pin "3") (pinfunction "+5V_3") (pintype "passive"))
      (node (ref "IS+5V") (pin "1") (pinfunction "1_1") (pintype "passive"))
      (node (ref "IS+5V") (pin "2") (pinfunction "2_2") (pintype "passive"))
      (node (ref "IS+5V") (pin "3") (pinfunction "3_3") (pintype "passive"))
      (node (ref "R48") (pin "2") (pinfunction "2_2") (pintype "passive"))
      (node (ref "U17") (pin "7") (pinfunction "+Vout_7") (pintype "passive"))
    )
    (net (code "22") (name "/LCD_D4") (class "Default")
      (node (ref "DUE") (pin "25") (pinfunction "25_25") (pintype "passive"))
      (node (ref "LCD") (pin "6") (pinfunction "D4_6") (pintype "passive"))
    )
    (net (code "23") (name "/LCD_D5") (class "Default")
      (node (ref "DUE") (pin "26") (pinfunction "26_26") (pintype "passive"))
      (node (ref "LCD") (pin "7") (pinfunction "D5_7") (pintype "passive"))
    )
    (net (code "24") (name "/LCD_D6") (class "Default")
      (node (ref "DUE") (pin "27") (pinfunction "27_27") (pintype "passive"))
      (node (ref "LCD") (pin "8") (pinfunction "D6_8") (pintype "passive"))
    )
    (net (code "25") (name "/LCD_D7") (class "Default")
      (node (ref "DUE") (pin "28") (pinfunction "28_28") (pintype "passive"))
      (node (ref "LCD") (pin "9") (pinfunction "D7_9") (pintype "passive"))
    )
    (net (code "26") (name "/LCD_E") (class "Default")
      (node (ref "DUE") (pin "24") (pinfunction "24_24") (pintype "passive"))
      (node (ref "LCD") (pin "5") (pinfunction "E_5") (pintype "passive"))
    )
    (net (code "27") (name "/LCD_RS") (class "Default")
      (node (ref "DUE") (pin "23") (pinfunction "23_23") (pintype "passive"))
      (node (ref "LCD") (pin "4") (pinfunction "RS_4") (pintype "passive"))
    )
    (net (code "28") (name "/MISO") (class "Default")
      (node (ref "DUE") (pin "ICSP_MISO") (pinfunction "ICSP_MISO_ICSP_MISO") (pintype "passive"))
      (node (ref "MICRO-SD") (pin "7") (pinfunction "DAT0(D0)_7") (pintype "passive"))
      (node (ref "NET") (pin "7") (pinfunction "MISO_7") (pintype "passive"))
      (node (ref "U7") (pin "2") (pinfunction "SO/SIO1_2") (pintype "passive"))
    )
    (net (code "29") (name "/MOSI") (class "Default")
      (node (ref "DUE") (pin "ICSP_MOSI") (pinfunction "ICSP_MOSI_ICSP_MOSI") (pintype "passive"))
      (node (ref "MICRO-SD") (pin "3") (pinfunction "CMD(DI)_3") (pintype "passive"))
      (node (ref "NET") (pin "3") (pinfunction "MOSI_3") (pintype "passive"))
      (node (ref "U7") (pin "5") (pinfunction "SI/SIO0_5") (pintype "passive"))
    )
    (net (code "30") (name "/OUT_A1") (class "Default")
      (node (ref "DUE") (pin "2") (pinfunction "2_2") (pintype "passive"))
      (node (ref "R20") (pin "1") (pinfunction "1_1") (pintype "passive"))
    )
    (net (code "31") (name "/OUT_A2") (class "Default")
      (node (ref "DUE") (pin "3") (pinfunction "3_3") (pintype "passive"))
      (node (ref "R19") (pin "2") (pinfunction "2_2") (pintype "passive"))
    )
    (net (code "32") (name "/PWM_O1") (class "Default")
      (node (ref "DUE") (pin "5") (pinfunction "5_5") (pintype "passive"))
      (node (ref "R47") (pin "1") (pinfunction "1_1") (pintype "passive"))
    )
    (net (code "33") (name "/PWM_O2") (class "Default")
      (node (ref "DUE") (pin "6") (pinfunction "6_6") (pintype "passive"))
      (node (ref "PWMO2") (pin "2") (pinfunction "2_2") (pintype "passive"))
    )
    (net (code "34") (name "/PWM_O3") (class "Default")
      (node (ref "DUE") (pin "7") (pinfunction "7_7") (pintype "passive"))
      (node (ref "PWMO2") (pin "3") (pinfunction "3_3") (pintype "passive"))
    )
    (net (code "35") (name "/PWM_O4") (class "Default")
      (node (ref "DUE") (pin "9") (pinfunction "9_9") (pintype "passive"))
      (node (ref "PWMO2") (pin "4") (pinfunction "4_4") (pintype "passive"))
    )
    (net (code "36") (name "/REL1") (class "Default")
      (node (ref "DUE") (pin "39") (pinfunction "39_39") (pintype "passive"))
      (node (ref "RELAY1") (pin "3") (pinfunction "3_3") (pintype "passive"))
    )
    (net (code "37") (name "/REL2") (class "Default")
      (node (ref "DUE") (pin "40") (pinfunction "40_40") (pintype "passive"))
      (node (ref "RELAY1") (pin "4") (pinfunction "4_4") (pintype "passive"))
    )
    (net (code "38") (name "/REL3") (class "Default")
      (node (ref "DUE") (pin "41") (pinfunction "41_41") (pintype "passive"))
      (node (ref "RELAY1") (pin "5") (pinfunction "5_5") (pintype "passive"))
    )
    (net (code "39") (name "/REL4") (class "Default")
      (node (ref "DUE") (pin "42") (pinfunction "42_42") (pintype "passive"))
      (node (ref "RELAY1") (pin "6") (pinfunction "6_6") (pintype "passive"))
    )
    (net (code "40") (name "/REL5") (class "Default")
      (node (ref "DUE") (pin "44") (pinfunction "44_44") (pintype "passive"))
      (node (ref "RELAY2") (pin "6") (pinfunction "6_6") (pintype "passive"))
    )
    (net (code "41") (name "/REL6") (class "Default")
      (node (ref "DUE") (pin "45") (pinfunction "45_45") (pintype "passive"))
      (node (ref "RELAY2") (pin "5") (pinfunction "5_5") (pintype "passive"))
    )
    (net (code "42") (name "/REL7") (class "Default")
      (node (ref "DUE") (pin "46") (pinfunction "46_46") (pintype "passive"))
      (node (ref "RELAY2") (pin "4") (pinfunction "4_4") (pintype "passive"))
    )
    (net (code "43") (name "/REL8") (class "Default")
      (node (ref "DUE") (pin "47") (pinfunction "47_47") (pintype "passive"))
      (node (ref "RELAY2") (pin "3") (pinfunction "3_3") (pintype "passive"))
    )
    (net (code "44") (name "/REL9") (class "Default")
      (node (ref "DUE") (pin "48") (pinfunction "48_48") (pintype "passive"))
      (node (ref "RELAY3") (pin "3") (pinfunction "3_3") (pintype "passive"))
    )
    (net (code "45") (name "/REL10") (class "Default")
      (node (ref "DUE") (pin "49") (pinfunction "49_49") (pintype "passive"))
      (node (ref "RELAY3") (pin "4") (pinfunction "4_4") (pintype "passive"))
    )
    (net (code "46") (name "/REL11") (class "Default")
      (node (ref "DUE") (pin "50") (pinfunction "50_50") (pintype "passive"))
      (node (ref "RELAY3") (pin "5") (pinfunction "5_5") (pintype "passive"))
    )
    (net (code "47") (name "/REL12") (class "Default")
      (node (ref "DUE") (pin "51") (pinfunction "51_51") (pintype "passive"))
      (node (ref "RELAY3") (pin "6") (pinfunction "6_6") (pintype "passive"))
    )
    (net (code "48") (name "/RELDC1") (class "Default")
      (node (ref "DUE") (pin "36") (pinfunction "36_36") (pintype "passive"))
      (node (ref "R43") (pin "1") (pinfunction "1_1") (pintype "passive"))
    )
    (net (code "49") (name "/RELDC2") (class "Default")
      (node (ref "DUE") (pin "37") (pinfunction "37_37") (pintype "passive"))
      (node (ref "R44") (pin "1") (pinfunction "1_1") (pintype "passive"))
    )
    (net (code "50") (name "/RXD1") (class "Default")
      (node (ref "DUE") (pin "15") (pinfunction "(RX1)15_15") (pintype "passive"))
      (node (ref "SER1") (pin "2") (pinfunction "RX_2") (pintype "passive"))
    )
    (net (code "51") (name "/RXD2") (class "Default")
      (node (ref "DUE") (pin "17") (pinfunction "(RX2)17_17") (pintype "passive"))
      (node (ref "SER2") (pin "2") (pinfunction "RX_2") (pintype "passive"))
    )
    (net (code "52") (name "/RXD3") (class "Default")
      (node (ref "DUE") (pin "19") (pinfunction "(RX3)19_19") (pintype "passive"))
      (node (ref "SER3") (pin "2") (pinfunction "RX_2") (pintype "passive"))
    )
    (net (code "53") (name "/RXD4") (class "Default")
      (node (ref "DUE") (pin "52") (pinfunction "52(CAN1_RX)_52") (pintype "passive"))
      (node (ref "SER4") (pin "2") (pinfunction "RX_2") (pintype "passive"))
    )
    (net (code "54") (name "/SCL") (class "Default")
      (node (ref "DUE") (pin "21") (pinfunction "(I2C0_SCL)21_21") (pintype "passive"))
      (node (ref "I2C_3.3V") (pin "4") (pinfunction "SCL_4") (pintype "passive"))
      (node (ref "U4") (pin "8") (pinfunction "SCL_8") (pintype "passive"))
      (node (ref "U5") (pin "5") (pinfunction "VL1_5") (pintype "passive"))
      (node (ref "U8") (pin "6") (pinfunction "SCL_6") (pintype "passive"))
    )
    (net (code "55") (name "/SCL1") (class "Default")
      (node (ref "DUE") (pin "SCL1") (pinfunction "I2C1_SCL_SCL1") (pintype "passive"))
      (node (ref "I2C1_3.3V") (pin "4") (pinfunction "SCL_4") (pintype "passive"))
      (node (ref "R49") (pin "2") (pinfunction "2_2") (pintype "passive"))
    )
    (net (code "56") (name "/SCLK") (class "Default")
      (node (ref "DUE") (pin "ICSP_SCK") (pinfunction "ICSP_SCK_ICSP_SCK") (pintype "passive"))
      (node (ref "MICRO-SD") (pin "5") (pinfunction "CLK(SCLK)_5") (pintype "passive"))
      (node (ref "NET") (pin "4") (pinfunction "SCLK_4") (pintype "passive"))
      (node (ref "U7") (pin "6") (pinfunction "SCLK_6") (pintype "passive"))
    )
    (net (code "57") (name "/SD-CS") (class "Default")
      (node (ref "DUE") (pin "4") (pinfunction "4_4") (pintype "passive"))
      (node (ref "MICRO-SD") (pin "2") (pinfunction "CDDAT3(CS)_2") (pintype "passive"))
    )
    (net (code "58") (name "/SDA") (class "Default")
      (node (ref "DUE") (pin "20") (pinfunction "(I2C0_SDA)20_20") (pintype "passive"))
      (node (ref "I2C_3.3V") (pin "3") (pinfunction "SDA_3") (pintype "passive"))
      (node (ref "U4") (pin "7") (pinfunction "SDA_7") (pintype "passive"))
      (node (ref "U5") (pin "4") (pinfunction "VL2_4") (pintype "passive"))
      (node (ref "U8") (pin "5") (pinfunction "SDA_5") (pintype "passive"))
    )
    (net (code "59") (name "/SDA1") (class "Default")
      (node (ref "DUE") (pin "SDA1") (pinfunction "I2C1_SDA_SDA1") (pintype "passive"))
      (node (ref "I2C1_3.3V") (pin "3") (pinfunction "SDA_3") (pintype "passive"))
      (node (ref "R50") (pin "2") (pinfunction "2_2") (pintype "passive"))
    )
    (net (code "60") (name "/TXD1") (class "Default")
      (node (ref "DUE") (pin "14") (pinfunction "(TX1)14_14") (pintype "passive"))
      (node (ref "SER1") (pin "3") (pinfunction "TX_3") (pintype "passive"))
    )
    (net (code "61") (name "/TXD2") (class "Default")
      (node (ref "DUE") (pin "16") (pinfunction "(TX2)16_16") (pintype "passive"))
      (node (ref "SER2") (pin "3") (pinfunction "TX_3") (pintype "passive"))
    )
    (net (code "62") (name "/TXD3") (class "Default")
      (node (ref "DUE") (pin "18") (pinfunction "(TX3)18_18") (pintype "passive"))
      (node (ref "SER3") (pin "3") (pinfunction "TX_3") (pintype "passive"))
    )
    (net (code "63") (name "/TXD4") (class "Default")
      (node (ref "DUE") (pin "A11") (pinfunction "A11_A11") (pintype "passive"))
      (node (ref "SER4") (pin "3") (pinfunction "TX_3") (pintype "passive"))
    )
    (net (code "64") (name "/ULN1") (class "Default")
      (node (ref "DUE") (pin "29") (pinfunction "29_29") (pintype "passive"))
      (node (ref "U6") (pin "1") (pinfunction "1B_1") (pintype "passive"))
    )
    (net (code "65") (name "/ULN2") (class "Default")
      (node (ref "DUE") (pin "30") (pinfunction "30_30") (pintype "passive"))
      (node (ref "U6") (pin "2") (pinfunction "2B_2") (pintype "passive"))
    )
    (net (code "66") (name "/ULN3") (class "Default")
      (node (ref "DUE") (pin "31") (pinfunction "31_31") (pintype "passive"))
      (node (ref "U6") (pin "3") (pinfunction "3B_3") (pintype "passive"))
    )
    (net (code "67") (name "/ULN4") (class "Default")
      (node (ref "DUE") (pin "32") (pinfunction "32_32") (pintype "passive"))
      (node (ref "U6") (pin "4") (pinfunction "4B_4") (pintype "passive"))
    )
    (net (code "68") (name "/ULN5") (class "Default")
      (node (ref "DUE") (pin "33") (pinfunction "33_33") (pintype "passive"))
      (node (ref "U6") (pin "5") (pinfunction "5B_5") (pintype "passive"))
    )
    (net (code "69") (name "/ULN6") (class "Default")
      (node (ref "DUE") (pin "34") (pinfunction "34_34") (pintype "passive"))
      (node (ref "U6") (pin "6") (pinfunction "6B_6") (pintype "passive"))
    )
    (net (code "70") (name "/ULN7") (class "Default")
      (node (ref "DUE") (pin "35") (pinfunction "35_35") (pintype "passive"))
      (node (ref "U6") (pin "7") (pinfunction "7B_7") (pintype "passive"))
    )
    (net (code "71") (name "/VIN(12V)") (class "Default")
      (node (ref "+12V") (pin "1") (pinfunction "GND_1") (pintype "passive"))
      (node (ref "+12V") (pin "2") (pinfunction "DQ_2") (pintype "passive"))
      (node (ref "+12V") (pin "3") (pinfunction "+5V_3") (pintype "passive"))
      (node (ref "BUZZER-12V") (pin "1") (pinfunction "+_1") (pintype "passive"))
      (node (ref "C15") (pin "2") (pinfunction "2_2") (pintype "passive"))
      (node (ref "C24") (pin "2") (pinfunction "2_2") (pintype "passive"))
      (node (ref "C25") (pin "2") (pinfunction "2_2") (pintype "passive"))
      (node (ref "DUE") (pin "VIN") (pinfunction "VIN_VIN") (pintype "passive"))
      (node (ref "L1") (pin "1") (pinfunction "1_1") (pintype "passive"))
      (node (ref "R2") (pin "1") (pinfunction "1_1") (pintype "passive"))
      (node (ref "U10") (pin "8") (pinfunction "VCC_8") (pintype "passive"))
    )
    (net (code "72") (name "Net-(DUE-(CAN1_TX)53)") (class "Default")
      (node (ref "DUE") (pin "53") (pinfunction "(CAN1_TX)53_53") (pintype "passive"))
      (node (ref "LED") (pin "2") (pinfunction "2_2") (pintype "passive"))
    )
    (net (code "73") (name "Net-(DUE-A12(DAC0))") (class "Default")
      (node (ref "DUE") (pin "A12") (pinfunction "A12(DAC0)_A12") (pintype "passive"))
      (node (ref "KEYS") (pin "2") (pinfunction "2_2") (pintype "passive"))
    )
    (net (code "74") (name "Net-(DUE-A13(DAC1))") (class "Default")
      (node (ref "DUE") (pin "A13") (pinfunction "A13(DAC1)_A13") (pintype "passive"))
      (node (ref "KEYS") (pin "3") (pinfunction "3_3") (pintype "passive"))
    )
    (net (code "75") (name "Net-(DUE-A14(CAN0_RX))") (class "Default")
      (node (ref "DUE") (pin "A14") (pinfunction "A14(CAN0_RX)_A14") (pintype "passive"))
      (node (ref "KEYS") (pin "4") (pinfunction "4_4") (pintype "passive"))
    )
    (net (code "76") (name "Net-(DUE-A15(CAN0_TX))") (class "Default")
      (node (ref "DUE") (pin "A15") (pinfunction "A15(CAN0_TX)_A15") (pintype "passive"))
      (node (ref "KEYS") (pin "5") (pinfunction "5_5") (pintype "passive"))
    )
    (net (code "77") (name "Net-(DUE-Pad11)") (class "Default")
      (node (ref "DUE") (pin "11") (pinfunction "11_11") (pintype "passive"))
      (node (ref "PWMO3") (pin "1") (pinfunction "1_1") (pintype "passive"))
    )
    (net (code "78") (name "Net-(DUE-Pad12)") (class "Default")
      (node (ref "DUE") (pin "12") (pinfunction "12_12") (pintype "passive"))
      (node (ref "PWMO3") (pin "2") (pinfunction "2_2") (pintype "passive"))
    )
    (net (code "79") (name "Net-(DUE-Pad13)") (class "Default")
      (node (ref "DUE") (pin "13") (pinfunction "13_13") (pintype "passive"))
      (node (ref "PWMO3") (pin "3") (pinfunction "3_3") (pintype "passive"))
    )
    (net (code "80") (name "Net-(DUE-Pad43)") (class "Default")
      (node (ref "DUE") (pin "43") (pinfunction "43_43") (pintype "passive"))
      (node (ref "R11") (pin "2") (pinfunction "2_2") (pintype "passive"))
    )
    (net (code "81") (name "Net-(I2C_5V-SCL)") (class "Default")
      (node (ref "I2C_5V") (pin "4") (pinfunction "SCL_4") (pintype "passive"))
      (node (ref "R4") (pin "1") (pinfunction "1_1") (pintype "passive"))
      (node (ref "U2") (pin "4") (pinfunction "SCL_4") (pintype "passive"))
      (node (ref "U3") (pin "4") (pinfunction "SCL_4") (pintype "passive"))
      (node (ref "U5") (pin "8") (pinfunction "VCC1_8") (pintype "passive"))
    )
    (net (code "82") (name "Net-(I2C_5V-SDA)") (class "Default")
      (node (ref "I2C_5V") (pin "3") (pinfunction "SDA_3") (pintype "passive"))
      (node (ref "R3") (pin "1") (pinfunction "1_1") (pintype "passive"))
      (node (ref "U2") (pin "5") (pinfunction "SDA_5") (pintype "passive"))
      (node (ref "U3") (pin "5") (pinfunction "SDA_5") (pintype "passive"))
      (node (ref "U5") (pin "1") (pinfunction "VCC2_1") (pintype "passive"))
    )
    (net (code "83") (name "Net-(INA1-Pad2)") (class "Default")
      (node (ref "INA1") (pin "2") (pinfunction "2_2") (pintype "passive"))
      (node (ref "R31") (pin "1") (pinfunction "1_1") (pintype "passive"))
    )
    (net (code "84") (name "Net-(INA2-Pad2)") (class "Default")
      (node (ref "INA2") (pin "2") (pinfunction "2_2") (pintype "passive"))
      (node (ref "R32") (pin "1") (pinfunction "1_1") (pintype "passive"))
    )
    (net (code "85") (name "Net-(INA3-Pad2)") (class "Default")
      (node (ref "INA3") (pin "2") (pinfunction "2_2") (pintype "passive"))
      (node (ref "R33") (pin "1") (pinfunction "1_1") (pintype "passive"))
    )
    (net (code "86") (name "Net-(INA4-Pad2)") (class "Default")
      (node (ref "INA4") (pin "2") (pinfunction "2_2") (pintype "passive"))
      (node (ref "R46") (pin "1") (pinfunction "1_1") (pintype "passive"))
    )
    (net (code "87") (name "Net-(INP1-DQ)") (class "Default")
      (node (ref "INP1") (pin "2") (pinfunction "DQ_2") (pintype "passive"))
      (node (ref "R42") (pin "1") (pinfunction "1_1") (pintype "passive"))
    )
    (net (code "88") (name "Net-(INP1-GND)") (class "Default")
      (node (ref "INP*.1->IS_GND") (pin "1") (pinfunction "1_1") (pintype "passive"))
      (node (ref "INP1") (pin "1") (pinfunction "GND_1") (pintype "passive"))
      (node (ref "U11") (pin "2") (pinfunction "CA_2") (pintype "passive"))
    )
    (net (code "89") (name "Net-(INP2-DQ)") (class "Default")
      (node (ref "INP2") (pin "2") (pinfunction "DQ_2") (pintype "passive"))
      (node (ref "R24") (pin "1") (pinfunction "1_1") (pintype "passive"))
    )
    (net (code "90") (name "Net-(INP2-GND)") (class "Default")
      (node (ref "INP*.1->IS_GND") (pin "2") (pinfunction "2_2") (pintype "passive"))
      (node (ref "INP2") (pin "1") (pinfunction "GND_1") (pintype "passive"))
      (node (ref "U12") (pin "2") (pinfunction "CA_2") (pintype "passive"))
    )
    (net (code "91") (name "Net-(INP3-DQ)") (class "Default")
      (node (ref "INP3") (pin "2") (pinfunction "DQ_2") (pintype "passive"))
      (node (ref "R26") (pin "1") (pinfunction "1_1") (pintype "passive"))
    )
    (net (code "92") (name "Net-(INP3-GND)") (class "Default")
      (node (ref "INP*.1->IS_GND") (pin "3") (pinfunction "3_3") (pintype "passive"))
      (node (ref "INP3") (pin "1") (pinfunction "GND_1") (pintype "passive"))
      (node (ref "U13") (pin "2") (pinfunction "CA_2") (pintype "passive"))
    )
    (net (code "93") (name "Net-(INP4C-DQ)") (class "Default")
      (node (ref "INP4C") (pin "2") (pinfunction "DQ_2") (pintype "passive"))
      (node (ref "R28") (pin "1") (pinfunction "1_1") (pintype "passive"))
    )
    (net (code "94") (name "Net-(INP4C-GND)") (class "Default")
      (node (ref "C11") (pin "2") (pinfunction "2_2") (pintype "passive"))
      (node (ref "INP*.1->IS_GND") (pin "4") (pinfunction "4_4") (pintype "passive"))
      (node (ref "INP4C") (pin "1") (pinfunction "GND_1") (pintype "passive"))
      (node (ref "U14") (pin "2") (pinfunction "CA_2") (pintype "passive"))
    )
    (net (code "95") (name "Net-(INP5C-DQ)") (class "Default")
      (node (ref "INP5C") (pin "2") (pinfunction "DQ_2") (pintype "passive"))
      (node (ref "R37") (pin "1") (pinfunction "1_1") (pintype "passive"))
    )
    (net (code "96") (name "Net-(INP5C-GND)") (class "Default")
      (node (ref "C28") (pin "2") (pinfunction "2_2") (pintype "passive"))
      (node (ref "INP*.1->IS_GND") (pin "5") (pinfunction "5_5") (pintype "passive"))
      (node (ref "INP5C") (pin "1") (pinfunction "GND_1") (pintype "passive"))
      (node (ref "U15") (pin "2") (pinfunction "CA_2") (pintype "passive"))
    )
    (net (code "97") (name "Net-(INP6C-DQ)") (class "Default")
      (node (ref "INP6C") (pin "2") (pinfunction "DQ_2") (pintype "passive"))
      (node (ref "R39") (pin "1") (pinfunction "1_1") (pintype "passive"))
    )
    (net (code "98") (name "Net-(INP6C-GND)") (class "Default")
      (node (ref "C29") (pin "2") (pinfunction "2_2") (pintype "passive"))
      (node (ref "INP*.1->IS_GND") (pin "6") (pinfunction "6_6") (pintype "passive"))
      (node (ref "INP6C") (pin "1") (pinfunction "GND_1") (pintype "passive"))
      (node (ref "U16") (pin "2") (pinfunction "CA_2") (pintype "passive"))
    )
    (net (code "99") (name "Net-(LCD-VEE)") (class "Default")
      (node (ref "LCD") (pin "3") (pinfunction "VEE_3") (pintype "passive"))
      (node (ref "R1") (pin "2") (pinfunction "2_2") (pintype "passive"))
    )
    (net (code "100") (name "Net-(LED-Pad1)") (class "Default")
      (node (ref "LED") (pin "1") (pinfunction "1_1") (pintype "passive"))
      (node (ref "R14") (pin "1") (pinfunction "1_1") (pintype "passive"))
    )
    (net (code "101") (name "Net-(PWMO1-+5V)") (class "Default")
      (node (ref "C27") (pin "2") (pinfunction "2_2") (pintype "passive"))
      (node (ref "PWMO1") (pin "3") (pinfunction "+5V_3") (pintype "passive"))
      (node (ref "U20") (pin "6") (pinfunction "6_6") (pintype "passive"))
    )
    (net (code "102") (name "Net-(PWMO1-DQ)") (class "Default")
      (node (ref "PWMO1") (pin "2") (pinfunction "DQ_2") (pintype "passive"))
      (node (ref "U20") (pin "5") (pinfunction "5_5") (pintype "passive"))
    )
    (net (code "103") (name "Net-(PWMO1-GND)") (class "Default")
      (node (ref "C27") (pin "1") (pinfunction "1_1") (pintype "passive"))
      (node (ref "PWMO1") (pin "1") (pinfunction "GND_1") (pintype "passive"))
      (node (ref "U20") (pin "4") (pinfunction "4_4") (pintype "passive"))
    )
    (net (code "104") (name "Net-(Q1-D)") (class "Default")
      (node (ref "D2") (pin "1") (pinfunction "1_1") (pintype "passive"))
      (node (ref "D2") (pin "2") (pinfunction "2_2") (pintype "passive"))
      (node (ref "Q1") (pin "3") (pinfunction "D_3") (pintype "passive"))
      (node (ref "R7") (pin "1") (pinfunction "1_1") (pintype "passive"))
      (node (ref "U3") (pin "2") (pinfunction "I0_2") (pintype "passive"))
    )
    (net (code "105") (name "Net-(Q1-G)") (class "Default")
      (node (ref "Q1") (pin "1") (pinfunction "G_1") (pintype "passive"))
      (node (ref "U3") (pin "6") (pinfunction "PCTLZ_6") (pintype "passive"))
    )
    (net (code "106") (name "Net-(Q4-B)") (class "Default")
      (node (ref "Q4") (pin "1") (pinfunction "B_1") (pintype "passive"))
      (node (ref "R11") (pin "1") (pinfunction "1_1") (pintype "passive"))
    )
    (net (code "107") (name "Net-(Q4-C)") (class "Default")
      (node (ref "BUZZER-12V") (pin "2") (pinfunction "2_2") (pintype "passive"))
      (node (ref "Q4") (pin "3") (pinfunction "C_3") (pintype "passive"))
    )
    (net (code "108") (name "Net-(R10-Pad2)") (class "Default")
      (node (ref "R10") (pin "2") (pinfunction "2_2") (pintype "passive"))
      (node (ref "R50") (pin "1") (pinfunction "1_1") (pintype "passive"))
    )
    (net (code "109") (name "Net-(R21-Pad3)") (class "Default")
      (node (ref "R21") (pin "3") (pinfunction "3_3") (pintype "passive"))
      (node (ref "R31") (pin "2") (pinfunction "2_2") (pintype "passive"))
    )
    (net (code "110") (name "Net-(R22-Pad3)") (class "Default")
      (node (ref "R22") (pin "3") (pinfunction "3_3") (pintype "passive"))
      (node (ref "R32") (pin "2") (pinfunction "2_2") (pintype "passive"))
    )
    (net (code "111") (name "Net-(R23-Pad3)") (class "Default")
      (node (ref "R23") (pin "3") (pinfunction "3_3") (pintype "passive"))
      (node (ref "R33") (pin "2") (pinfunction "2_2") (pintype "passive"))
    )
    (net (code "112") (name "Net-(R45-Pad3)") (class "Default")
      (node (ref "R45") (pin "3") (pinfunction "3_3") (pintype "passive"))
      (node (ref "R46") (pin "2") (pinfunction "2_2") (pintype "passive"))
    )
    (net (code "113") (name "Net-(R47-Pad2)") (class "Default")
      (node (ref "R47") (pin "2") (pinfunction "2_2") (pintype "passive"))
      (node (ref "U20") (pin "1") (pinfunction "1_1") (pintype "passive"))
    )
    (net (code "114") (name "Net-(R49-Pad1)") (class "Default")
      (node (ref "R49") (pin "1") (pinfunction "1_1") (pintype "passive"))
      (node (ref "R9") (pin "2") (pinfunction "2_2") (pintype "passive"))
    )
    (net (code "115") (name "Net-(T1-DQ)") (class "Default")
      (node (ref "R5") (pin "2") (pinfunction "2_2") (pintype "passive"))
      (node (ref "T1") (pin "2") (pinfunction "DQ_2") (pintype "passive"))
      (node (ref "T2") (pin "2") (pinfunction "DQ_2") (pintype "passive"))
    )
    (net (code "116") (name "Net-(T1-GND)") (class "Default")
      (node (ref "D3") (pin "3") (pinfunction "3_3") (pintype "passive"))
      (node (ref "R6") (pin "2") (pinfunction "2_2") (pintype "passive"))
      (node (ref "T1") (pin "1") (pinfunction "GND_1") (pintype "passive"))
      (node (ref "T2") (pin "1") (pinfunction "GND_1") (pintype "passive"))
    )
    (net (code "117") (name "Net-(TP1-DQ)") (class "Default")
      (node (ref "R7") (pin "2") (pinfunction "2_2") (pintype "passive"))
      (node (ref "TP1") (pin "2") (pinfunction "DQ_2") (pintype "passive"))
    )
    (net (code "118") (name "Net-(TP1-GND)") (class "Default")
      (node (ref "R8") (pin "2") (pinfunction "2_2") (pintype "passive"))
      (node (ref "TP1") (pin "1") (pinfunction "GND_1") (pintype "passive"))
    )
    (net (code "119") (name "Net-(U2-I0)") (class "Default")
      (node (ref "D1") (pin "1") (pinfunction "1_1") (pintype "passive"))
      (node (ref "D1") (pin "2") (pinfunction "2_2") (pintype "passive"))
      (node (ref "R5") (pin "1") (pinfunction "1_1") (pintype "passive"))
      (node (ref "U2") (pin "2") (pinfunction "I0_2") (pintype "passive"))
    )
    (net (code "120") (name "Net-(U4-VBAT)") (class "Default")
      (node (ref "B1") (pin "1") (pinfunction "1_1") (pintype "passive"))
      (node (ref "U4") (pin "6") (pinfunction "VBAT_6") (pintype "passive"))
    )
    (net (code "121") (name "Net-(U6-1C)") (class "Default")
      (node (ref "U6") (pin "16") (pinfunction "1C_16") (pintype "passive"))
      (node (ref "ULN(EEV)") (pin "2") (pinfunction "2_2") (pintype "passive"))
    )
    (net (code "122") (name "Net-(U6-2C)") (class "Default")
      (node (ref "U6") (pin "15") (pinfunction "2C_15") (pintype "passive"))
      (node (ref "ULN(EEV)1") (pin "1") (pinfunction "1_1") (pintype "passive"))
    )
    (net (code "123") (name "Net-(U6-3C)") (class "Default")
      (node (ref "U6") (pin "14") (pinfunction "3C_14") (pintype "passive"))
      (node (ref "ULN(EEV)1") (pin "2") (pinfunction "2_2") (pintype "passive"))
    )
    (net (code "124") (name "Net-(U6-4C)") (class "Default")
      (node (ref "U6") (pin "13") (pinfunction "4C_13") (pintype "passive"))
      (node (ref "ULN(EEV)2") (pin "1") (pinfunction "1_1") (pintype "passive"))
    )
    (net (code "125") (name "Net-(U6-5C)") (class "Default")
      (node (ref "U6") (pin "12") (pinfunction "5C_12") (pintype "passive"))
      (node (ref "ULN(EEV)2") (pin "2") (pinfunction "2_2") (pintype "passive"))
    )
    (net (code "126") (name "Net-(U6-6C)") (class "Default")
      (node (ref "U6") (pin "11") (pinfunction "6C_11") (pintype "passive"))
      (node (ref "ULN(EEV)3") (pin "1") (pinfunction "1_1") (pintype "passive"))
    )
    (net (code "127") (name "Net-(U6-7C)") (class "Default")
      (node (ref "U6") (pin "10") (pinfunction "7C_10") (pintype "passive"))
      (node (ref "ULN(EEV)3") (pin "2") (pinfunction "2_2") (pintype "passive"))
    )
    (net (code "128") (name "Net-(U6-COM)") (class "Default")
      (node (ref "C14") (pin "2") (pinfunction "2_2") (pintype "passive"))
      (node (ref "R13") (pin "2") (pinfunction "2_2") (pintype "passive"))
      (node (ref "R2") (pin "2") (pinfunction "2_2") (pintype "passive"))
      (node (ref "U6") (pin "9") (pinfunction "COM_9") (pintype "passive"))
      (node (ref "ULN(EEV)") (pin "1") (pinfunction "1_1") (pintype "passive"))
    )
    (net (code "129") (name "Net-(U7-WP#)") (class "Default")
      (node (ref "R12") (pin "2") (pinfunction "2_2") (pintype "passive"))
      (node (ref "U7") (pin "3") (pinfunction "WP#_3") (pintype "passive"))
    )
    (net (code "130") (name "Net-(U10-1IN+)") (class "Default")
      (node (ref "C17") (pin "2") (pinfunction "2_2") (pintype "passive"))
      (node (ref "R20") (pin "2") (pinfunction "2_2") (pintype "passive"))
      (node (ref "U10") (pin "3") (pinfunction "1IN+_3") (pintype "passive"))
    )
    (net (code "131") (name "Net-(U10-1IN-)") (class "Default")
      (node (ref "R16") (pin "2") (pinfunction "2_2") (pintype "passive"))
      (node (ref "R18") (pin "1") (pinfunction "1_1") (pintype "passive"))
      (node (ref "U10") (pin "2") (pinfunction "1IN-_2") (pintype "passive"))
    )
    (net (code "132") (name "Net-(U10-1OUT)") (class "Default")
      (node (ref "OUTA1") (pin "2") (pinfunction "2_2") (pintype "passive"))
      (node (ref "R18") (pin "2") (pinfunction "2_2") (pintype "passive"))
      (node (ref "U10") (pin "1") (pinfunction "1OUT_1") (pintype "passive"))
    )
    (net (code "133") (name "Net-(U10-2IN+)") (class "Default")
      (node (ref "C16") (pin "1") (pinfunction "1_1") (pintype "passive"))
      (node (ref "R19") (pin "1") (pinfunction "1_1") (pintype "passive"))
      (node (ref "U10") (pin "5") (pinfunction "2IN+_5") (pintype "passive"))
    )
    (net (code "134") (name "Net-(U10-2IN-)") (class "Default")
      (node (ref "R15") (pin "2") (pinfunction "2_2") (pintype "passive"))
      (node (ref "R17") (pin "1") (pinfunction "1_1") (pintype "passive"))
      (node (ref "U10") (pin "6") (pinfunction "2IN-_6") (pintype "passive"))
    )
    (net (code "135") (name "Net-(U10-2OUT)") (class "Default")
      (node (ref "OUTA2") (pin "2") (pinfunction "2_2") (pintype "passive"))
      (node (ref "R17") (pin "2") (pinfunction "2_2") (pintype "passive"))
      (node (ref "U10") (pin "7") (pinfunction "2OUT_7") (pintype "passive"))
    )
    (net (code "136") (name "Net-(U11-AN)") (class "Default")
      (node (ref "R42") (pin "2") (pinfunction "2_2") (pintype "passive"))
      (node (ref "U11") (pin "1") (pinfunction "AN_1") (pintype "passive"))
    )
    (net (code "137") (name "Net-(U12-AN)") (class "Default")
      (node (ref "R24") (pin "2") (pinfunction "2_2") (pintype "passive"))
      (node (ref "U12") (pin "1") (pinfunction "AN_1") (pintype "passive"))
    )
    (net (code "138") (name "Net-(U13-AN)") (class "Default")
      (node (ref "R26") (pin "2") (pinfunction "2_2") (pintype "passive"))
      (node (ref "U13") (pin "1") (pinfunction "AN_1") (pintype "passive"))
    )
    (net (code "139") (name "Net-(U14-AN)") (class "Default")
      (node (ref "C11") (pin "1") (pinfunction "1_1") (pintype "passive"))
      (node (ref "R28") (pin "2") (pinfunction "2_2") (pintype "passive"))
      (node (ref "U14") (pin "1") (pinfunction "AN_1") (pintype "passive"))
    )
    (net (code "140") (name "Net-(U15-AN)") (class "Default")
      (node (ref "C28") (pin "1") (pinfunction "1_1") (pintype "passive"))
      (node (ref "R37") (pin "2") (pinfunction "2_2") (pintype "passive"))
      (node (ref "U15") (pin "1") (pinfunction "AN_1") (pintype "passive"))
    )
    (net (code "141") (name "Net-(U16-AN)") (class "Default")
      (node (ref "C29") (pin "1") (pinfunction "1_1") (pintype "passive"))
      (node (ref "R39") (pin "2") (pinfunction "2_2") (pintype "passive"))
      (node (ref "U16") (pin "1") (pinfunction "AN_1") (pintype "passive"))
    )
    (net (code "142") (name "Net-(U17-+Vin)") (class "Default")
      (node (ref "L1") (pin "2") (pinfunction "2_2") (pintype "passive"))
      (node (ref "U17") (pin "1") (pinfunction "+Vin_1") (pintype "passive"))
    )
    (net (code "143") (name "Net-(U17--Vout)") (class "Default")
      (node (ref "C26") (pin "2") (pinfunction "2_2") (pintype "passive"))
      (node (ref "INP*.1->IS_GND") (pin "10") (pinfunction "10_10") (pintype "passive"))
      (node (ref "INP*.1->IS_GND") (pin "11") (pinfunction "11_11") (pintype "passive"))
      (node (ref "INP*.1->IS_GND") (pin "12") (pinfunction "12_12") (pintype "passive"))
      (node (ref "INP*.1->IS_GND") (pin "7") (pinfunction "7_7") (pintype "passive"))
      (node (ref "INP*.1->IS_GND") (pin "8") (pinfunction "8_8") (pintype "passive"))
      (node (ref "INP*.1->IS_GND") (pin "9") (pinfunction "9_9") (pintype "passive"))
      (node (ref "IS_GND") (pin "1") (pinfunction "1_1") (pintype "passive"))
      (node (ref "IS_GND") (pin "2") (pinfunction "2_2") (pintype "passive"))
      (node (ref "IS_GND") (pin "3") (pinfunction "3_3") (pintype "passive"))
      (node (ref "R48") (pin "1") (pinfunction "1_1") (pintype "passive"))
      (node (ref "U17") (pin "5") (pinfunction "-Vout_5") (pintype "passive"))
    )
    (net (code "144") (name "Net-(U18-AN)") (class "Default")
      (node (ref "R43") (pin "2") (pinfunction "2_2") (pintype "passive"))
      (node (ref "U18") (pin "1") (pinfunction "AN_1") (pintype "passive"))
    )
    (net (code "145") (name "Net-(U18-COL)") (class "Default")
      (node (ref "RELDC1") (pin "2") (pinfunction "2_2") (pintype "passive"))
      (node (ref "U18") (pin "4") (pinfunction "COL_4") (pintype "passive"))
    )
    (net (code "146") (name "Net-(U18-EM)") (class "Default")
      (node (ref "RELDC1") (pin "1") (pinfunction "1_1") (pintype "passive"))
      (node (ref "U18") (pin "3") (pinfunction "EM_3") (pintype "passive"))
    )
    (net (code "147") (name "Net-(U19-AN)") (class "Default")
      (node (ref "R44") (pin "2") (pinfunction "2_2") (pintype "passive"))
      (node (ref "U19") (pin "1") (pinfunction "AN_1") (pintype "passive"))
    )
    (net (code "148") (name "Net-(U19-COL)") (class "Default")
      (node (ref "RELDC2") (pin "2") (pinfunction "2_2") (pintype "passive"))
      (node (ref "U19") (pin "4") (pinfunction "COL_4") (pintype "passive"))
    )
    (net (code "149") (name "Net-(U19-EM)") (class "Default")
      (node (ref "RELDC2") (pin "1") (pinfunction "1_1") (pintype "passive"))
      (node (ref "U19") (pin "3") (pinfunction "EM_3") (pintype "passive"))
    )
    (net (code "150") (name "unconnected-(DUE-(RX0)0-Pad0)") (class "Default")
      (node (ref "DUE") (pin "0") (pinfunction "(RX0)0_0") (pintype "passive+no_connect"))
    )
    (net (code "151") (name "unconnected-(DUE-(TX0)1-Pad1)") (class "Default")
      (node (ref "DUE") (pin "1") (pinfunction "(TX0)1_1") (pintype "passive+no_connect"))
    )
    (net (code "152") (name "unconnected-(DUE-PadICSP_RESET)") (class "Default")
      (node (ref "DUE") (pin "ICSP_RESET") (pinfunction "ICSP_RESET_ICSP_RESET") (pintype "passive+no_connect"))
    )
    (net (code "153") (name "unconnected-(DUE-PadRESET)") (class "Default")
      (node (ref "DUE") (pin "RESET") (pinfunction "RESET_RESET") (pintype "passive+no_connect"))
    )
    (net (code "154") (name "unconnected-(DUE-RFU(RAW)-PadRFU)") (class "Default")
      (node (ref "DUE") (pin "RFU") (pinfunction "RFU(RAW)_RFU") (pintype "passive+no_connect"))
    )
    (net (code "155") (name "unconnected-(MICRO-SD-CD-Pad9)") (class "Default")
      (node (ref "MICRO-SD") (pin "9") (pinfunction "CD_9") (pintype "passive+no_connect"))
    )
    (net (code "156") (name "unconnected-(MICRO-SD-DAT1(RSV)-Pad8)") (class "Default")
      (node (ref "MICRO-SD") (pin "8") (pinfunction "DAT1(RSV)_8") (pintype "passive+no_connect"))
    )
    (net (code "157") (name "unconnected-(MICRO-SD-DAT2(RSV)-Pad1)") (class "Default")
      (node (ref "MICRO-SD") (pin "1") (pinfunction "DAT2(RSV)_1") (pintype "passive+no_connect"))
    )
    (net (code "158") (name "unconnected-(NET-INT-Pad6)") (class "Default")
      (node (ref "NET") (pin "6") (pinfunction "INT_6") (pintype "passive+no_connect"))
    )
    (net (code "159") (name "unconnected-(NET-NC-Pad9)") (class "Default")
      (node (ref "NET") (pin "9") (pinfunction "NC_9") (pintype "passive+no_connect"))
    )
    (net (code "160") (name "unconnected-(U2-PCTLZ-Pad6)") (class "Default")
      (node (ref "U2") (pin "6") (pinfunction "PCTLZ_6") (pintype "passive+no_connect"))
    )
    (net (code "161") (name "unconnected-(U4-32kHz-Pad1)") (class "Default")
      (node (ref "U4") (pin "1") (pinfunction "32kHz_1") (pintype "passive+no_connect"))
    )
    (net (code "162") (name "unconnected-(U4-INT#{slash}SQW-Pad3)") (class "Default")
      (node (ref "U4") (pin "3") (pinfunction "INT#/SQW_3") (pintype "passive+no_connect"))
    )
    (net (code "163") (name "unconnected-(U4-RST#-Pad4)") (class "Default")
      (node (ref "U4") (pin "4") (pinfunction "RST#_4") (pintype "passive+no_connect"))
    )
    (net (code "164") (name "unconnected-(U8-DU-Pad1)") (class "Default")
      (node (ref "U8") (pin "1") (pinfunction "DU_1") (pintype "passive+no_connect"))
    )
  )
)
